# power_v1.net
KiCad netlist of a schematic drawn in EAGLE
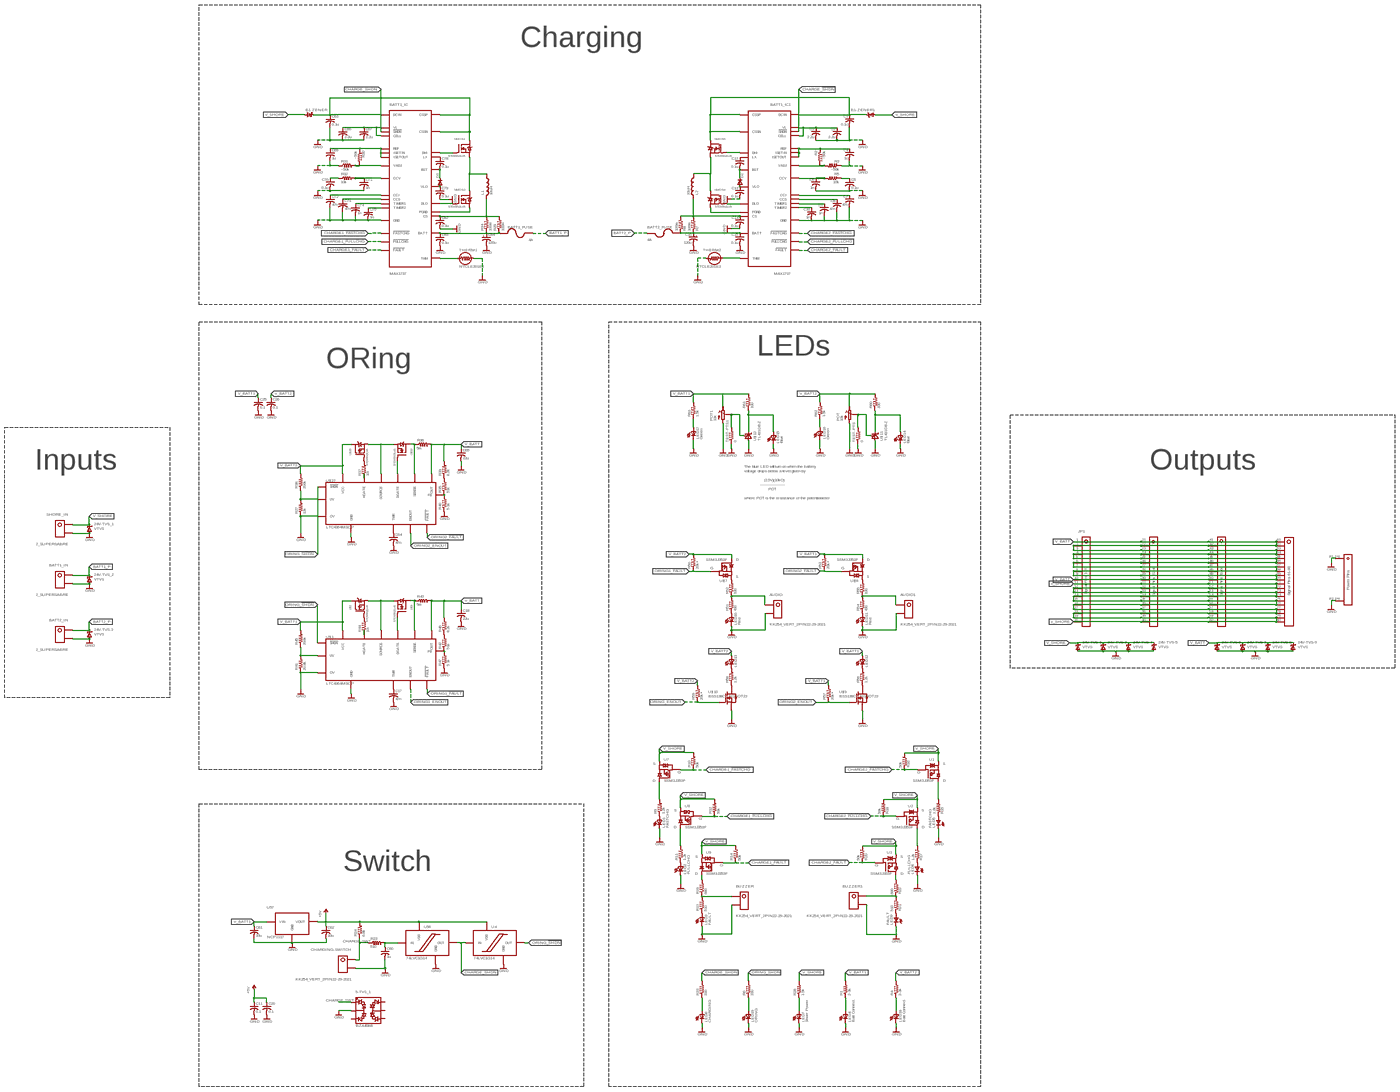
[diagram p0: schematic, sheet 1, overview]
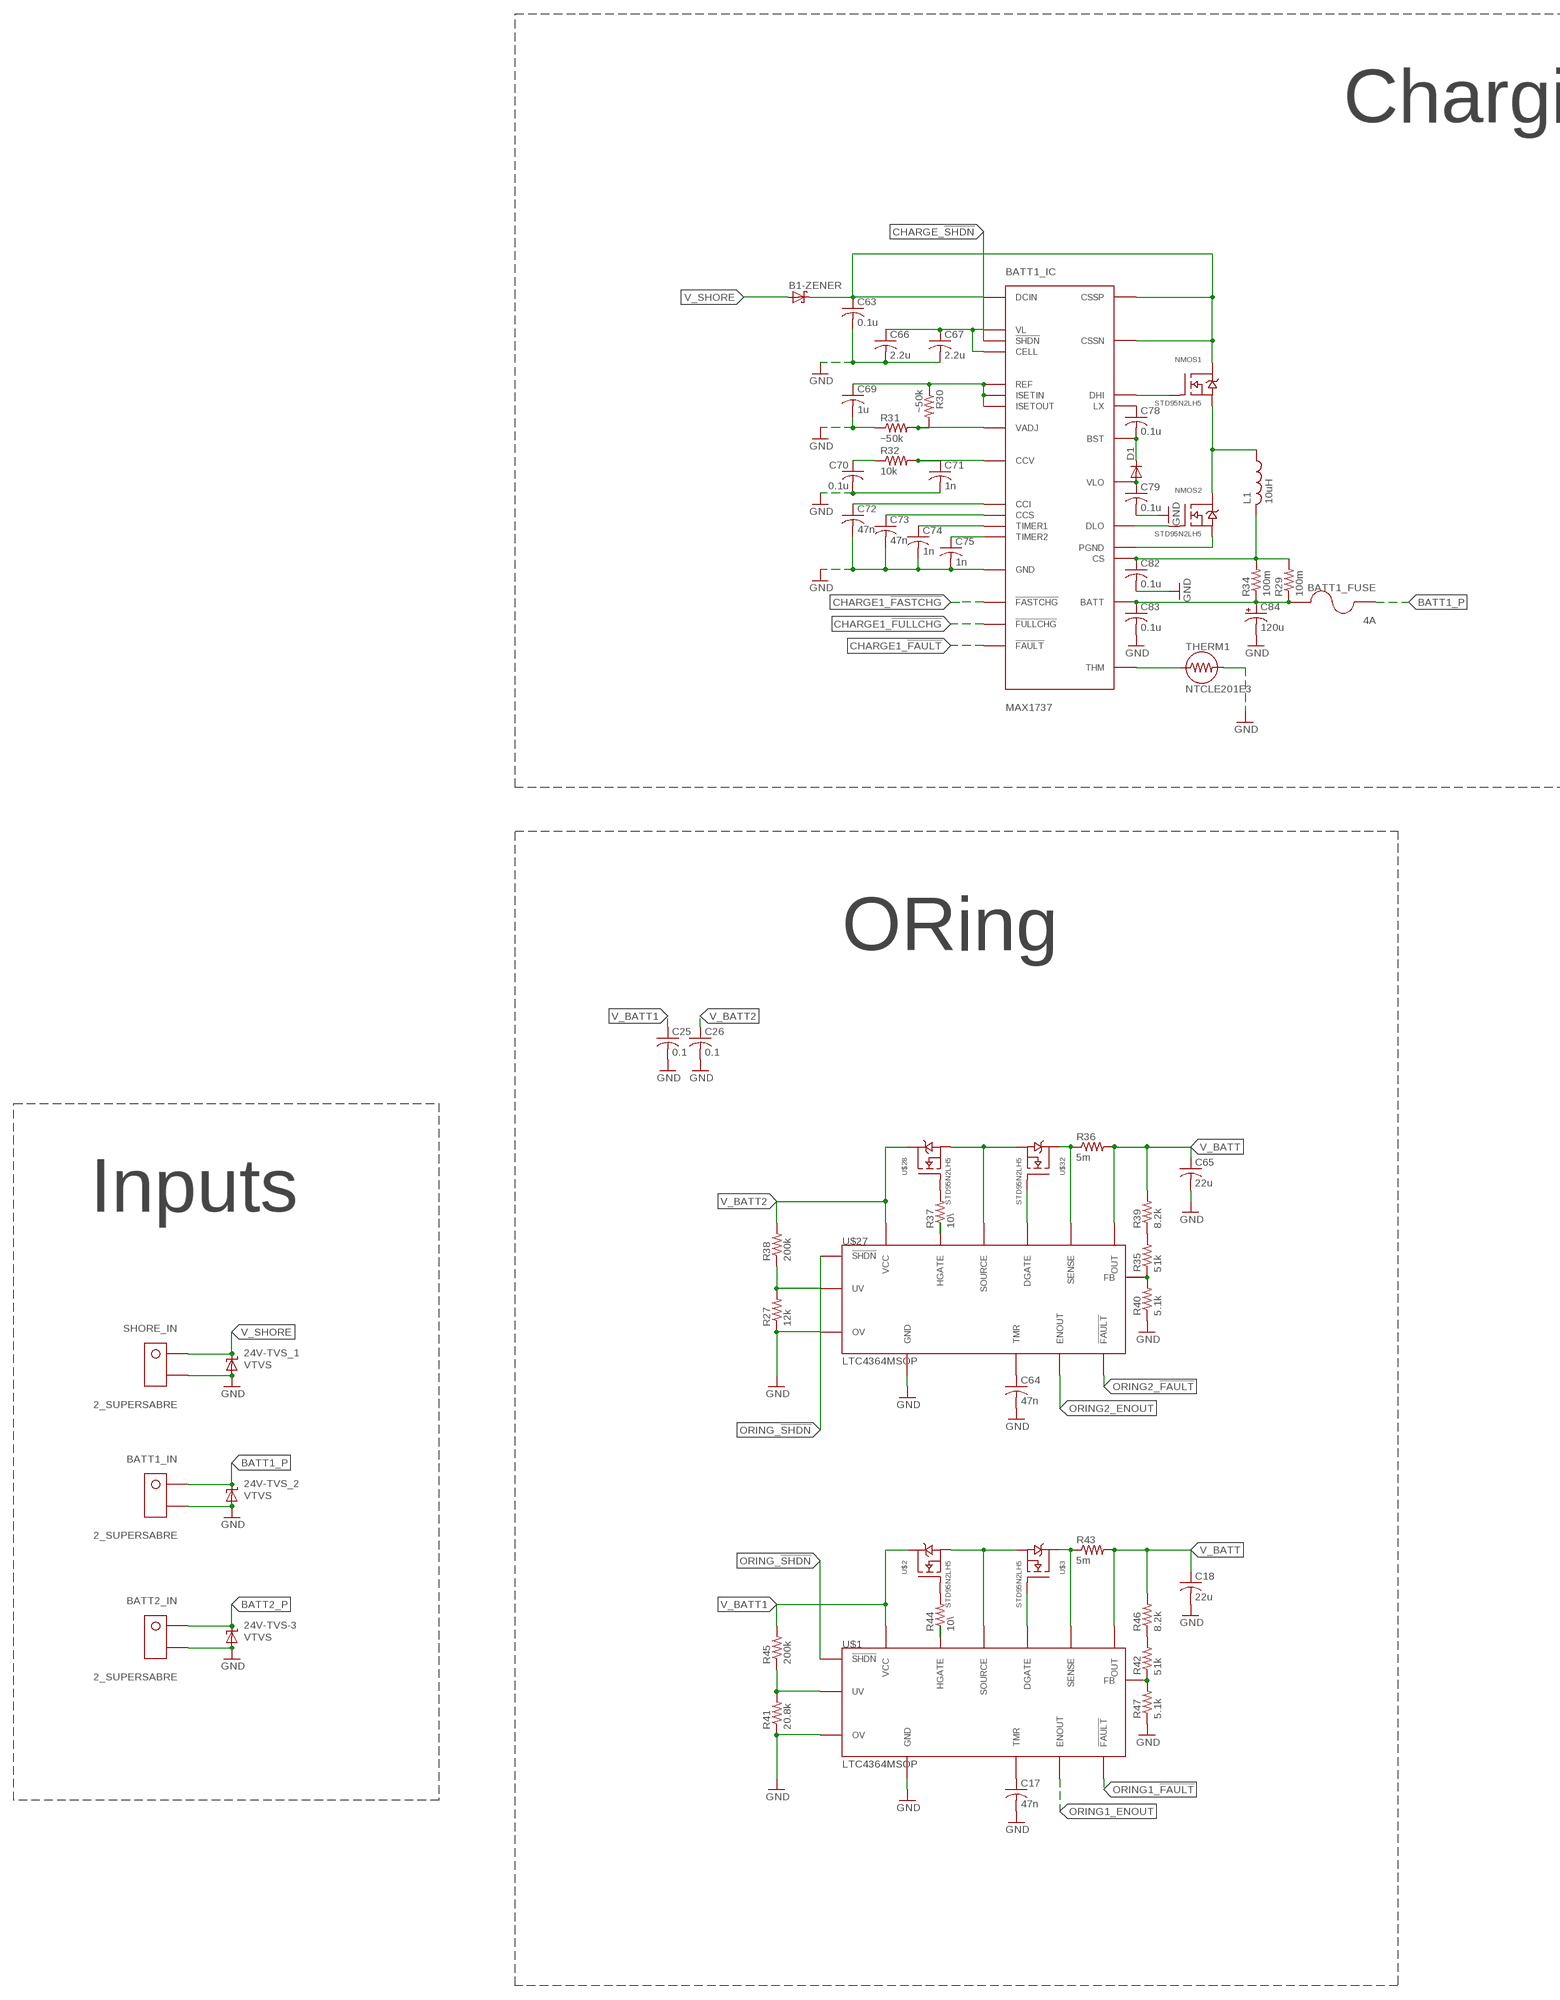
[diagram p1: schematic, sheet 1, part 1 of 4]
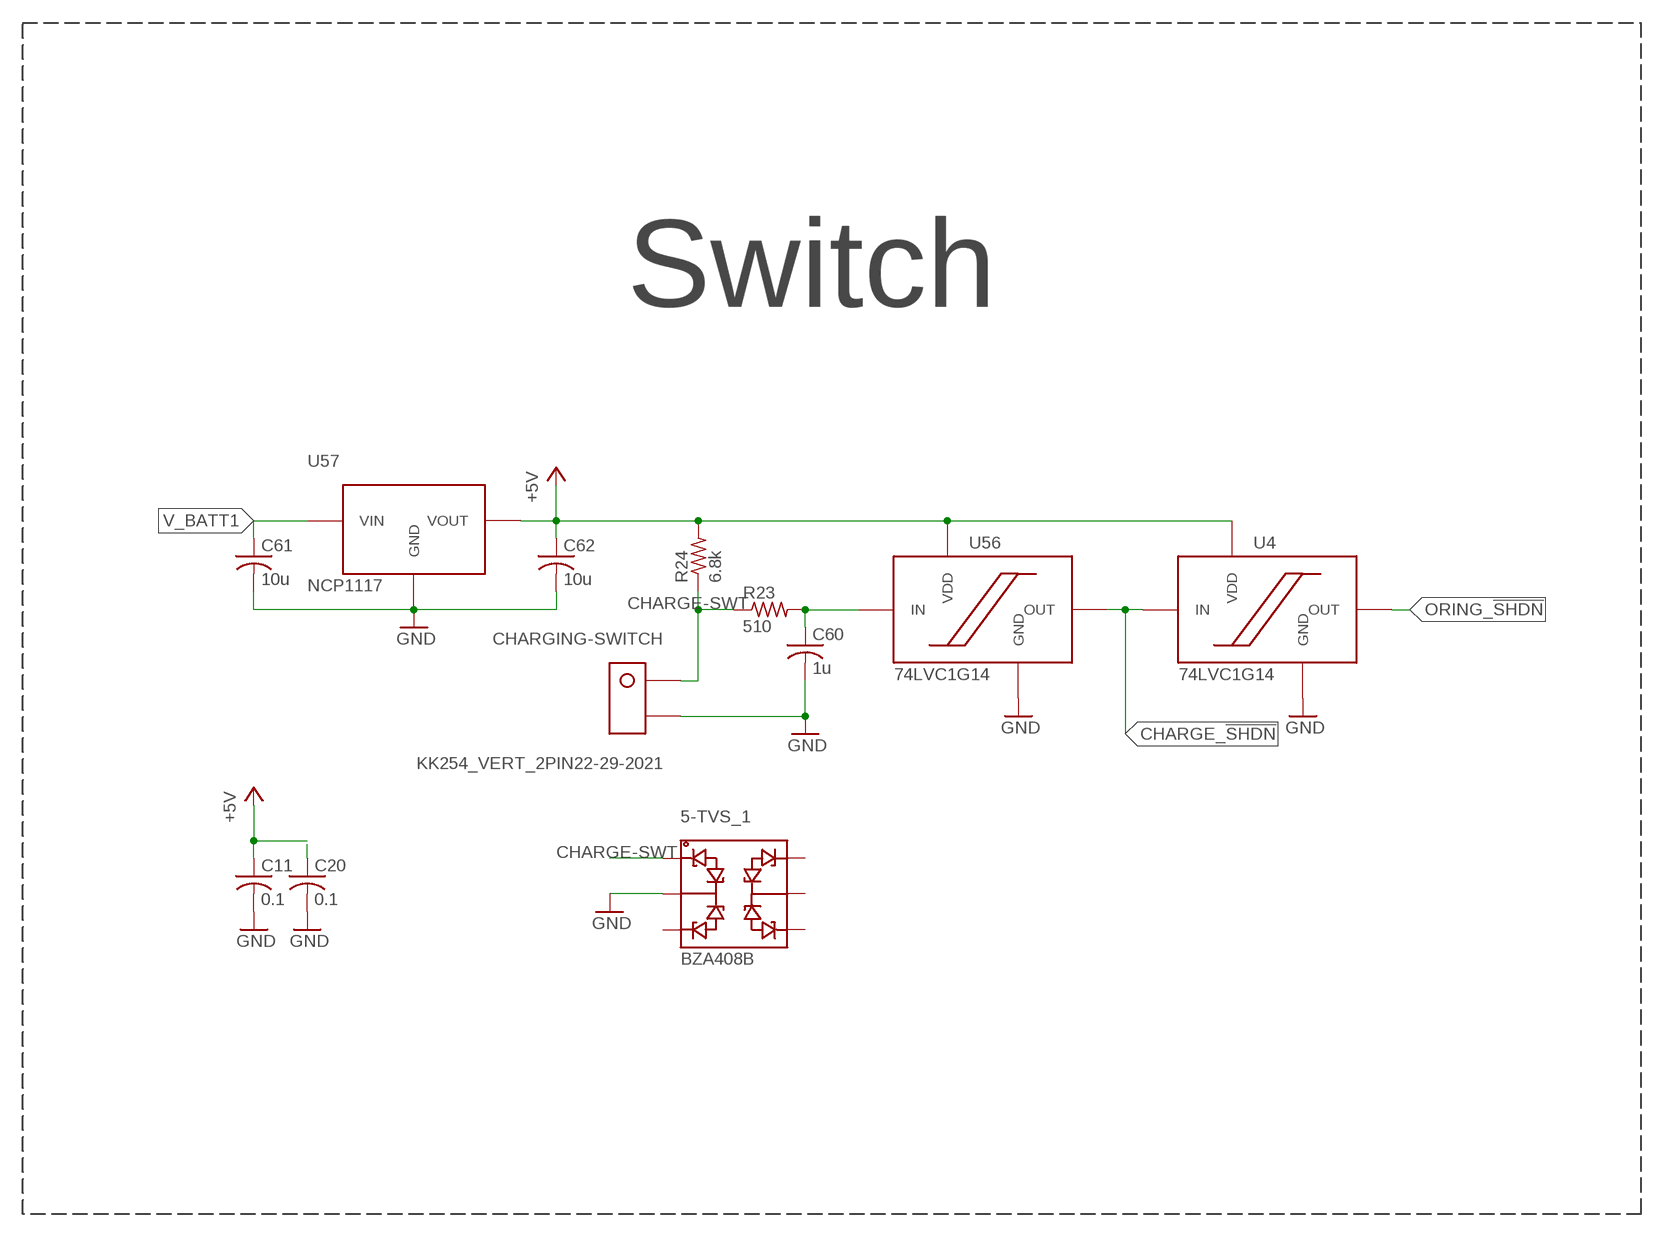
[diagram p2: schematic, sheet 1, part 2 of 4]
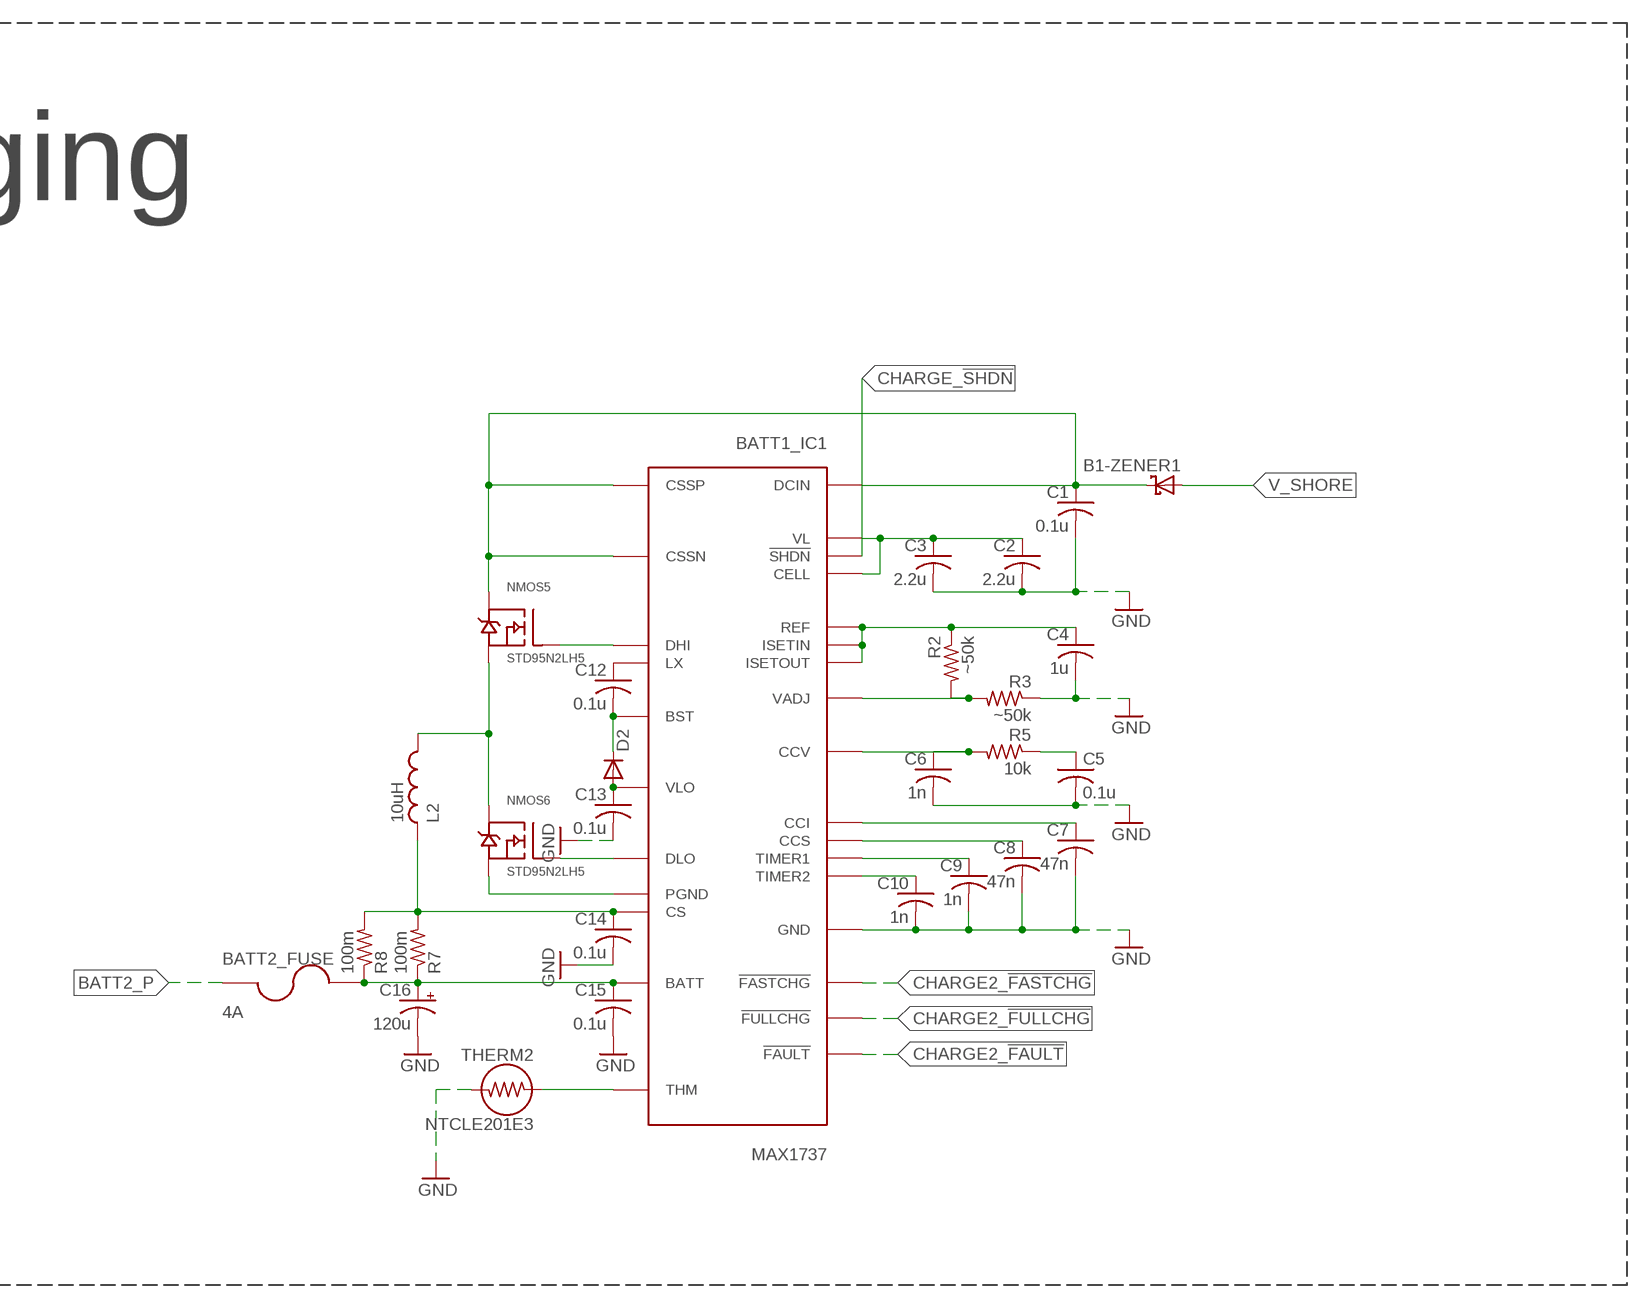
[diagram p3: schematic, sheet 1, part 3 of 4]
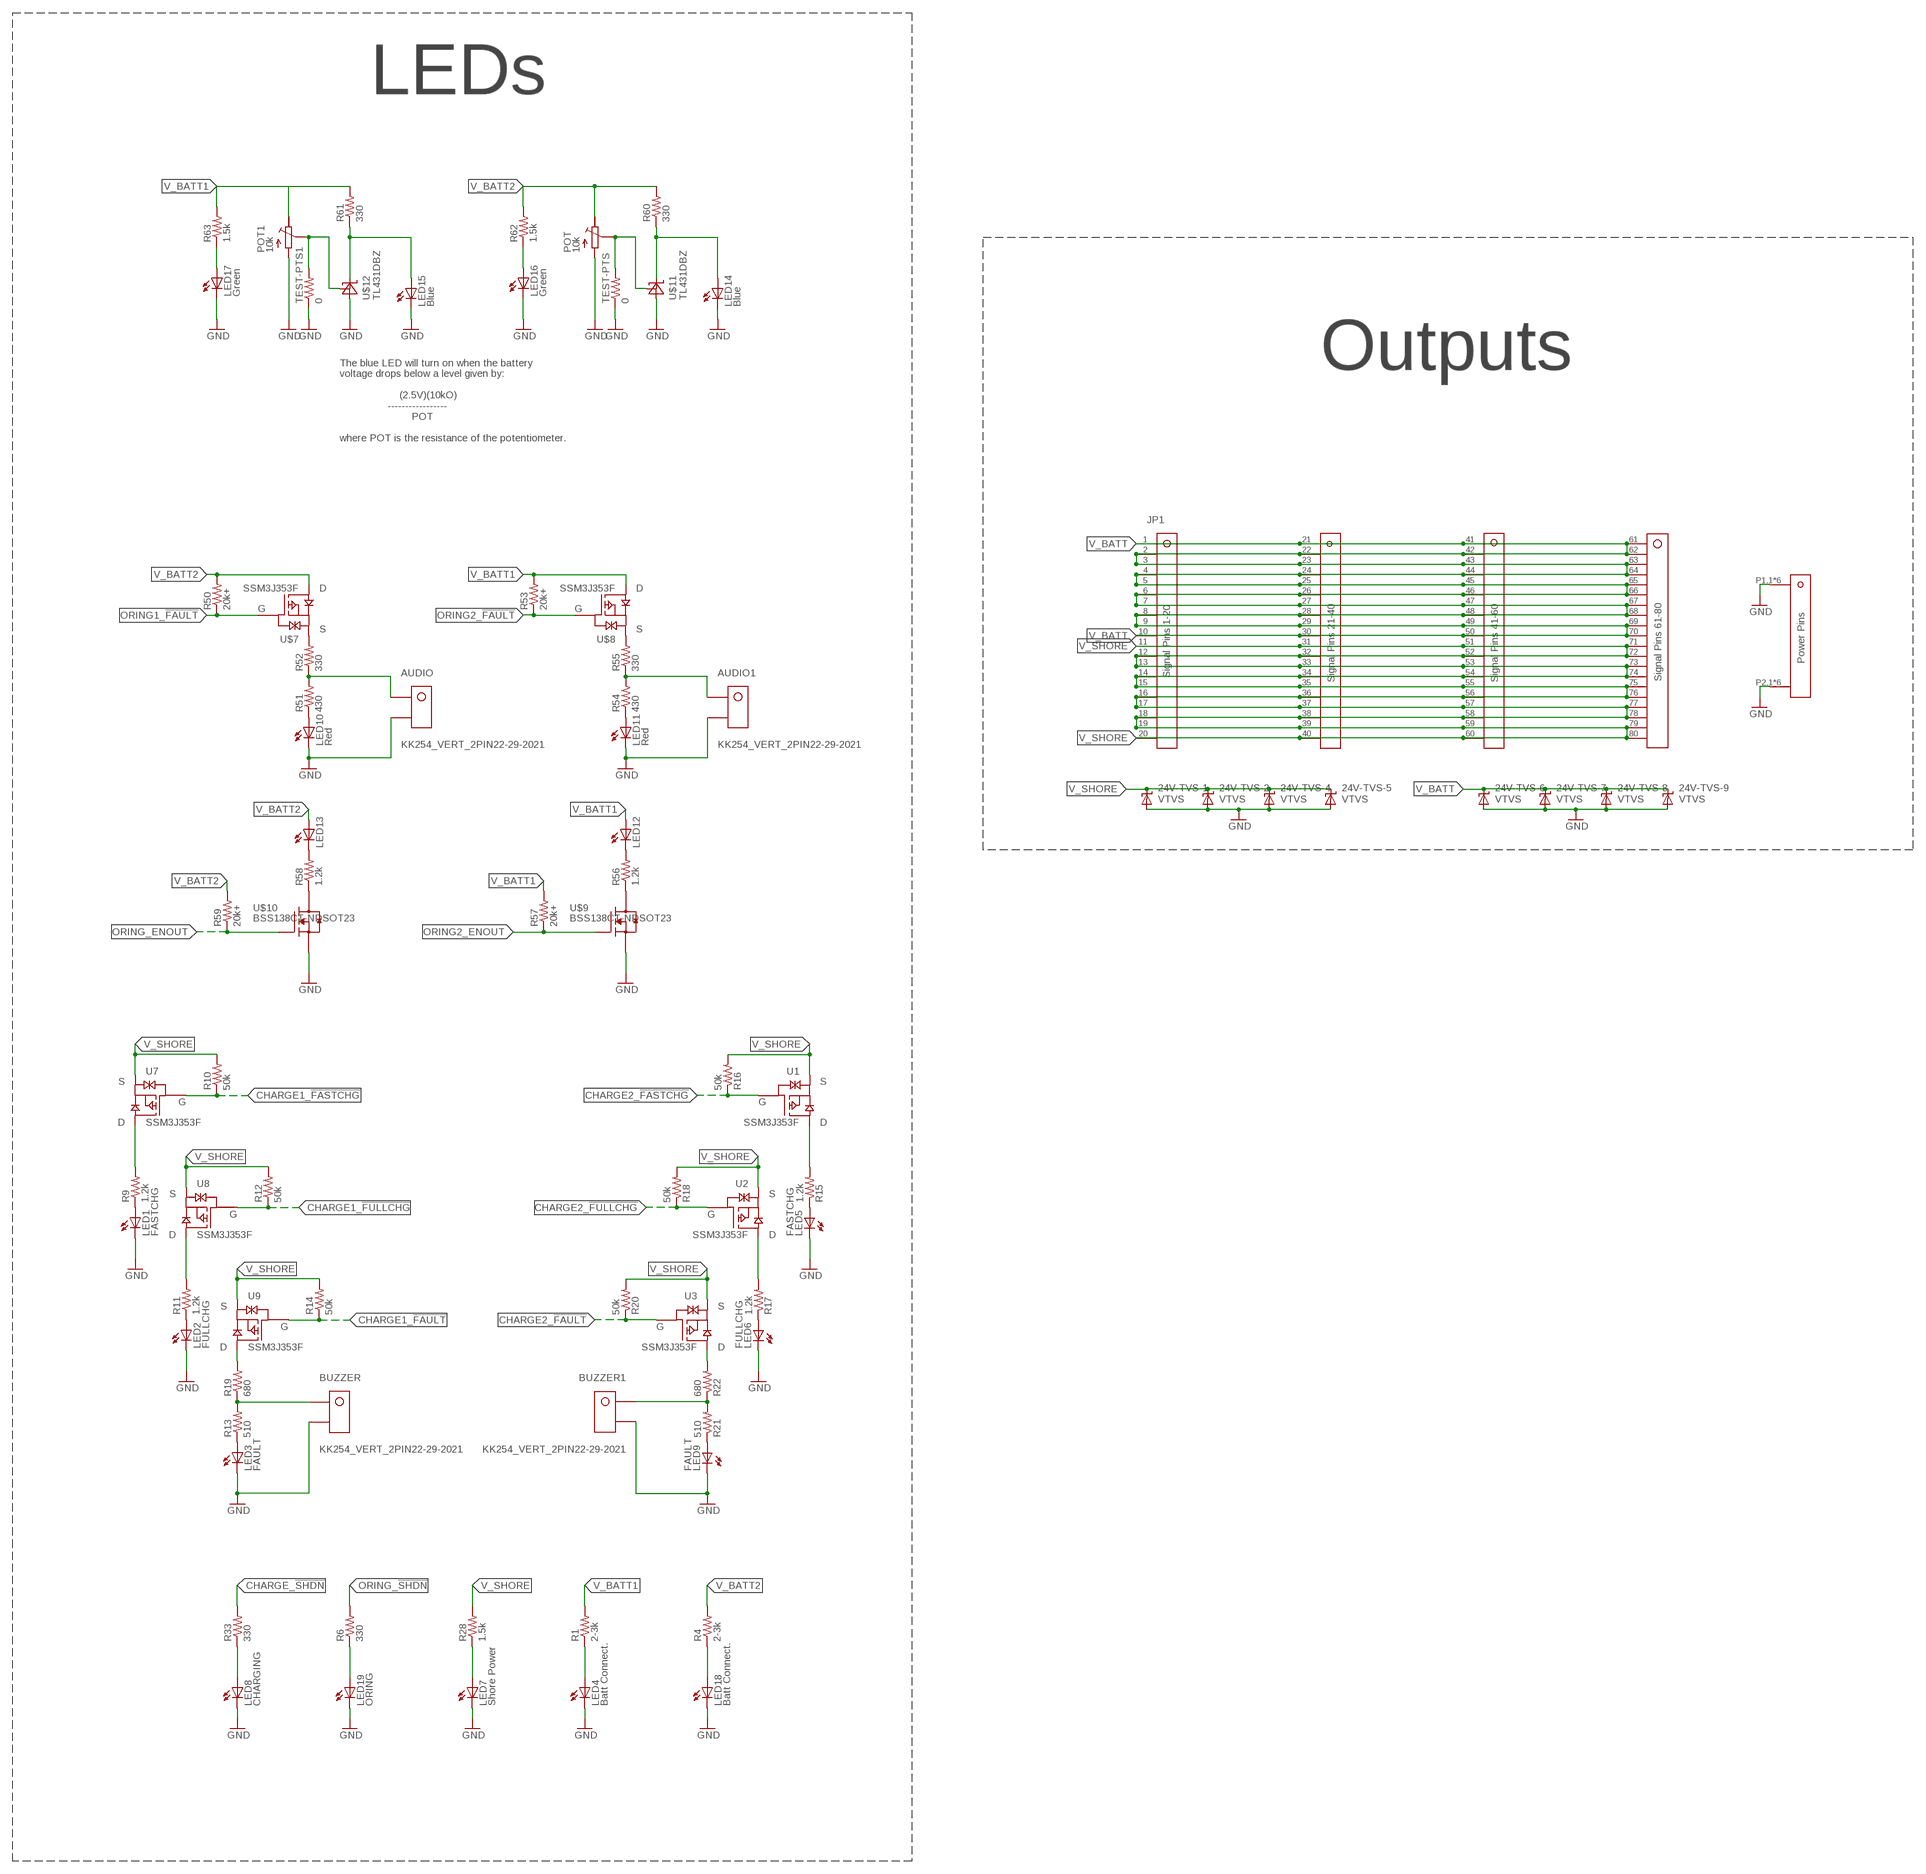
[diagram p4: schematic, sheet 1, part 4 of 4]

(export (version "E")
  (design (tool "Eeschema 10.0.6"))
  (components
    (comp (ref "5-TVS_1")
      (value "BZA408B")
      (footprint "eagle-import:SOT457")
      (libsource (lib "eagle-import") (part "BZA408B"))
    )
    (comp (ref "24V-TVS-1")
      (value "VTVS")
      (footprint "eagle-import:DO-219AB")
      (libsource (lib "eagle-import") (part "VTVS"))
    )
    (comp (ref "24V-TVS-2")
      (value "VTVS")
      (footprint "eagle-import:DO-219AB")
      (libsource (lib "eagle-import") (part "VTVS"))
    )
    (comp (ref "24V-TVS-3")
      (value "VTVS")
      (footprint "eagle-import:DO-219AB")
      (libsource (lib "eagle-import") (part "VTVS"))
    )
    (comp (ref "24V-TVS-4")
      (value "VTVS")
      (footprint "eagle-import:DO-219AB")
      (libsource (lib "eagle-import") (part "VTVS"))
    )
    (comp (ref "24V-TVS-5")
      (value "VTVS")
      (footprint "eagle-import:DO-219AB")
      (libsource (lib "eagle-import") (part "VTVS"))
    )
    (comp (ref "24V-TVS-6")
      (value "VTVS")
      (footprint "eagle-import:DO-219AB")
      (libsource (lib "eagle-import") (part "VTVS"))
    )
    (comp (ref "24V-TVS-7")
      (value "VTVS")
      (footprint "eagle-import:DO-219AB")
      (libsource (lib "eagle-import") (part "VTVS"))
    )
    (comp (ref "24V-TVS-8")
      (value "VTVS")
      (footprint "eagle-import:DO-219AB")
      (libsource (lib "eagle-import") (part "VTVS"))
    )
    (comp (ref "24V-TVS-9")
      (value "VTVS")
      (footprint "eagle-import:DO-219AB")
      (libsource (lib "eagle-import") (part "VTVS"))
    )
    (comp (ref "24V-TVS_1")
      (value "VTVS")
      (footprint "eagle-import:DO-219AB")
      (libsource (lib "eagle-import") (part "VTVS"))
    )
    (comp (ref "24V-TVS_2")
      (value "VTVS")
      (footprint "eagle-import:DO-219AB")
      (libsource (lib "eagle-import") (part "VTVS"))
    )
    (comp (ref "AUDIO")
      (value "KK254_VERT_2PIN22-29-2021")
      (footprint "eagle-import:KK254_VERT_2PIN")
      (libsource (lib "eagle-import") (part "KK254_VERT_2PIN22-29-2021"))
    )
    (comp (ref "AUDIO1")
      (value "KK254_VERT_2PIN22-29-2021")
      (footprint "eagle-import:KK254_VERT_2PIN")
      (libsource (lib "eagle-import") (part "KK254_VERT_2PIN22-29-2021"))
    )
    (comp (ref "B1-ZENER")
      (value "SCHOTTKY-DIODESOD-106")
      (footprint "eagle-import:SOD106-R")
      (libsource (lib "eagle-import") (part "SCHOTTKY-DIODESOD-106"))
    )
    (comp (ref "B1-ZENER1")
      (value "SCHOTTKY-DIODESOD-106")
      (footprint "eagle-import:SOD106-R")
      (libsource (lib "eagle-import") (part "SCHOTTKY-DIODESOD-106"))
    )
    (comp (ref "BATT1_FUSE")
      (value "4A")
      (footprint "eagle-import:154-OMNI-BLOK")
      (libsource (lib "eagle-import") (part "154-OMNI_BLOK"))
    )
    (comp (ref "BATT1_IC")
      (value "MAX1737")
      (footprint "eagle-import:QSOP28")
      (libsource (lib "eagle-import") (part "MAX1737"))
    )
    (comp (ref "BATT1_IC1")
      (value "MAX1737")
      (footprint "eagle-import:QSOP28")
      (libsource (lib "eagle-import") (part "MAX1737"))
    )
    (comp (ref "BATT1_IN")
      (value "2_SUPERSABRE")
      (footprint "eagle-import:SUPERSABRE_2CIRCUIT")
      (libsource (lib "eagle-import") (part "2_SUPERSABRE"))
    )
    (comp (ref "BATT2_FUSE")
      (value "4A")
      (footprint "eagle-import:154-OMNI-BLOK")
      (libsource (lib "eagle-import") (part "154-OMNI_BLOK"))
    )
    (comp (ref "BATT2_IN")
      (value "2_SUPERSABRE")
      (footprint "eagle-import:SUPERSABRE_2CIRCUIT")
      (libsource (lib "eagle-import") (part "2_SUPERSABRE"))
    )
    (comp (ref "BUZZER")
      (value "KK254_VERT_2PIN22-29-2021")
      (footprint "eagle-import:KK254_VERT_2PIN")
      (libsource (lib "eagle-import") (part "KK254_VERT_2PIN22-29-2021"))
    )
    (comp (ref "BUZZER1")
      (value "KK254_VERT_2PIN22-29-2021")
      (footprint "eagle-import:KK254_VERT_2PIN")
      (libsource (lib "eagle-import") (part "KK254_VERT_2PIN22-29-2021"))
    )
    (comp (ref "C1")
      (value "0.1u")
      (footprint "eagle-import:C0805")
      (libsource (lib "eagle-import") (part "C-USC0805"))
    )
    (comp (ref "C2")
      (value "2.2u")
      (footprint "eagle-import:C0805")
      (libsource (lib "eagle-import") (part "C-USC0805"))
    )
    (comp (ref "C3")
      (value "2.2u")
      (footprint "eagle-import:C0805")
      (libsource (lib "eagle-import") (part "C-USC0805"))
    )
    (comp (ref "C4")
      (value "1u")
      (footprint "eagle-import:C0805")
      (libsource (lib "eagle-import") (part "C-USC0805"))
    )
    (comp (ref "C5")
      (value "0.1u")
      (footprint "eagle-import:C0805")
      (libsource (lib "eagle-import") (part "C-USC0805"))
    )
    (comp (ref "C6")
      (value "1n")
      (footprint "eagle-import:C0805")
      (libsource (lib "eagle-import") (part "C-USC0805"))
    )
    (comp (ref "C7")
      (value "47n")
      (footprint "eagle-import:C0805")
      (libsource (lib "eagle-import") (part "C-USC0805"))
    )
    (comp (ref "C8")
      (value "47n")
      (footprint "eagle-import:C0805")
      (libsource (lib "eagle-import") (part "C-USC0805"))
    )
    (comp (ref "C9")
      (value "1n")
      (footprint "eagle-import:C0805")
      (libsource (lib "eagle-import") (part "C-USC0805"))
    )
    (comp (ref "C10")
      (value "1n")
      (footprint "eagle-import:C0805")
      (libsource (lib "eagle-import") (part "C-USC0805"))
    )
    (comp (ref "C11")
      (value "0.1")
      (footprint "eagle-import:C0805")
      (libsource (lib "eagle-import") (part "C-USC0805"))
    )
    (comp (ref "C12")
      (value "0.1u")
      (footprint "eagle-import:C0805")
      (libsource (lib "eagle-import") (part "C-USC0805"))
    )
    (comp (ref "C13")
      (value "0.1u")
      (footprint "eagle-import:C0805")
      (libsource (lib "eagle-import") (part "C-USC0805"))
    )
    (comp (ref "C14")
      (value "0.1u")
      (footprint "eagle-import:C0805")
      (libsource (lib "eagle-import") (part "C-USC0805"))
    )
    (comp (ref "C15")
      (value "0.1u")
      (footprint "eagle-import:C0805")
      (libsource (lib "eagle-import") (part "C-USC0805"))
    )
    (comp (ref "C16")
      (value "120u")
      (footprint "eagle-import:E3,5-8")
      (libsource (lib "eagle-import") (part "CPOL-USE3.5-8"))
    )
    (comp (ref "C17")
      (value "47n")
      (footprint "eagle-import:C0805")
      (libsource (lib "eagle-import") (part "C-USC0805"))
    )
    (comp (ref "C18")
      (value "22u")
      (footprint "eagle-import:C0805")
      (libsource (lib "eagle-import") (part "C-USC0805"))
    )
    (comp (ref "C20")
      (value "0.1")
      (footprint "eagle-import:C0805")
      (libsource (lib "eagle-import") (part "C-USC0805"))
    )
    (comp (ref "C25")
      (value "0.1")
      (footprint "eagle-import:C0805")
      (libsource (lib "eagle-import") (part "C-USC0805"))
    )
    (comp (ref "C26")
      (value "0.1")
      (footprint "eagle-import:C0805")
      (libsource (lib "eagle-import") (part "C-USC0805"))
    )
    (comp (ref "C60")
      (value "1u")
      (footprint "eagle-import:C0805")
      (libsource (lib "eagle-import") (part "C-USC0805"))
    )
    (comp (ref "C61")
      (value "10u")
      (footprint "eagle-import:C0805")
      (libsource (lib "eagle-import") (part "C-USC0805"))
    )
    (comp (ref "C62")
      (value "10u")
      (footprint "eagle-import:C0805")
      (libsource (lib "eagle-import") (part "C-USC0805"))
    )
    (comp (ref "C63")
      (value "0.1u")
      (footprint "eagle-import:C0805")
      (libsource (lib "eagle-import") (part "C-USC0805"))
    )
    (comp (ref "C64")
      (value "47n")
      (footprint "eagle-import:C0805")
      (libsource (lib "eagle-import") (part "C-USC0805"))
    )
    (comp (ref "C65")
      (value "22u")
      (footprint "eagle-import:C0805")
      (libsource (lib "eagle-import") (part "C-USC0805"))
    )
    (comp (ref "C66")
      (value "2.2u")
      (footprint "eagle-import:C0805")
      (libsource (lib "eagle-import") (part "C-USC0805"))
    )
    (comp (ref "C67")
      (value "2.2u")
      (footprint "eagle-import:C0805")
      (libsource (lib "eagle-import") (part "C-USC0805"))
    )
    (comp (ref "C69")
      (value "1u")
      (footprint "eagle-import:C0805")
      (libsource (lib "eagle-import") (part "C-USC0805"))
    )
    (comp (ref "C70")
      (value "0.1u")
      (footprint "eagle-import:C0805")
      (libsource (lib "eagle-import") (part "C-USC0805"))
    )
    (comp (ref "C71")
      (value "1n")
      (footprint "eagle-import:C0805")
      (libsource (lib "eagle-import") (part "C-USC0805"))
    )
    (comp (ref "C72")
      (value "47n")
      (footprint "eagle-import:C0805")
      (libsource (lib "eagle-import") (part "C-USC0805"))
    )
    (comp (ref "C73")
      (value "47n")
      (footprint "eagle-import:C0805")
      (libsource (lib "eagle-import") (part "C-USC0805"))
    )
    (comp (ref "C74")
      (value "1n")
      (footprint "eagle-import:C0805")
      (libsource (lib "eagle-import") (part "C-USC0805"))
    )
    (comp (ref "C75")
      (value "1n")
      (footprint "eagle-import:C0805")
      (libsource (lib "eagle-import") (part "C-USC0805"))
    )
    (comp (ref "C78")
      (value "0.1u")
      (footprint "eagle-import:C0805")
      (libsource (lib "eagle-import") (part "C-USC0805"))
    )
    (comp (ref "C79")
      (value "0.1u")
      (footprint "eagle-import:C0805")
      (libsource (lib "eagle-import") (part "C-USC0805"))
    )
    (comp (ref "C82")
      (value "0.1u")
      (footprint "eagle-import:C0805")
      (libsource (lib "eagle-import") (part "C-USC0805"))
    )
    (comp (ref "C83")
      (value "0.1u")
      (footprint "eagle-import:C0805")
      (libsource (lib "eagle-import") (part "C-USC0805"))
    )
    (comp (ref "C84")
      (value "120u")
      (footprint "eagle-import:E3,5-8")
      (libsource (lib "eagle-import") (part "CPOL-USE3.5-8"))
    )
    (comp (ref "CHARGING-SWITCH")
      (value "KK254_VERT_2PIN22-29-2021")
      (footprint "eagle-import:KK254_VERT_2PIN")
      (libsource (lib "eagle-import") (part "KK254_VERT_2PIN22-29-2021"))
    )
    (comp (ref "D1")
      (value "DIODE-SOD123")
      (footprint "eagle-import:SOD123")
      (libsource (lib "eagle-import") (part "DIODE-SOD123"))
    )
    (comp (ref "D2")
      (value "DIODE-SOD123")
      (footprint "eagle-import:SOD123")
      (libsource (lib "eagle-import") (part "DIODE-SOD123"))
    )
    (comp (ref "JP1")
      (value "MPSC-01-80MPSC-RA-LC")
      (footprint "eagle-import:MPSC-01-80")
      (libsource (lib "eagle-import") (part "MPSC-01-80MPSC-RA-LC"))
    )
    (comp (ref "L1")
      (value "10uH")
      (footprint "eagle-import:L6100")
      (libsource (lib "eagle-import") (part "L-USL6100"))
    )
    (comp (ref "L2")
      (value "10uH")
      (footprint "eagle-import:L6100")
      (libsource (lib "eagle-import") (part "L-USL6100"))
    )
    (comp (ref "LED1")
      (value "FASTCHG")
      (footprint "eagle-import:CHIP-LED0805")
      (libsource (lib "eagle-import") (part "LEDCHIP-LED0805"))
    )
    (comp (ref "LED2")
      (value "FULLCHG")
      (footprint "eagle-import:CHIP-LED0805")
      (libsource (lib "eagle-import") (part "LEDCHIP-LED0805"))
    )
    (comp (ref "LED3")
      (value "FAULT")
      (footprint "eagle-import:CHIP-LED0805")
      (libsource (lib "eagle-import") (part "LEDCHIP-LED0805"))
    )
    (comp (ref "LED4")
      (value "Batt Connect.")
      (footprint "eagle-import:CHIP-LED0805")
      (libsource (lib "eagle-import") (part "LEDCHIP-LED0805"))
    )
    (comp (ref "LED5")
      (value "FASTCHG")
      (footprint "eagle-import:CHIP-LED0805")
      (libsource (lib "eagle-import") (part "LEDCHIP-LED0805"))
    )
    (comp (ref "LED6")
      (value "FULLCHG")
      (footprint "eagle-import:CHIP-LED0805")
      (libsource (lib "eagle-import") (part "LEDCHIP-LED0805"))
    )
    (comp (ref "LED7")
      (value "Shore Power")
      (footprint "eagle-import:CHIP-LED0805")
      (libsource (lib "eagle-import") (part "LEDCHIP-LED0805"))
    )
    (comp (ref "LED8")
      (value "CHARGING")
      (footprint "eagle-import:CHIP-LED0805")
      (libsource (lib "eagle-import") (part "LEDCHIP-LED0805"))
    )
    (comp (ref "LED9")
      (value "FAULT")
      (footprint "eagle-import:CHIP-LED0805")
      (libsource (lib "eagle-import") (part "LEDCHIP-LED0805"))
    )
    (comp (ref "LED10")
      (value "Red")
      (footprint "eagle-import:CHIPLED_0805")
      (libsource (lib "eagle-import") (part "LEDCHIPLED_0805"))
    )
    (comp (ref "LED11")
      (value "Red")
      (footprint "eagle-import:CHIPLED_0805")
      (libsource (lib "eagle-import") (part "LEDCHIPLED_0805"))
    )
    (comp (ref "LED12")
      (value "LEDCHIPLED_0805")
      (footprint "eagle-import:CHIPLED_0805")
      (libsource (lib "eagle-import") (part "LEDCHIPLED_0805"))
    )
    (comp (ref "LED13")
      (value "LEDCHIPLED_0805")
      (footprint "eagle-import:CHIPLED_0805")
      (libsource (lib "eagle-import") (part "LEDCHIPLED_0805"))
    )
    (comp (ref "LED14")
      (value "Blue")
      (footprint "eagle-import:0805")
      (libsource (lib "eagle-import") (part "0805_LED"))
    )
    (comp (ref "LED15")
      (value "Blue")
      (footprint "eagle-import:0805")
      (libsource (lib "eagle-import") (part "0805_LED"))
    )
    (comp (ref "LED16")
      (value "Green")
      (footprint "eagle-import:0805")
      (libsource (lib "eagle-import") (part "0805_LED"))
    )
    (comp (ref "LED17")
      (value "Green")
      (footprint "eagle-import:0805")
      (libsource (lib "eagle-import") (part "0805_LED"))
    )
    (comp (ref "LED18")
      (value "Batt Connect.")
      (footprint "eagle-import:CHIP-LED0805")
      (libsource (lib "eagle-import") (part "LEDCHIP-LED0805"))
    )
    (comp (ref "LED19")
      (value "ORING")
      (footprint "eagle-import:CHIP-LED0805")
      (libsource (lib "eagle-import") (part "LEDCHIP-LED0805"))
    )
    (comp (ref "NMOS1")
      (value "STD95N2LH5")
      (footprint "eagle-import:DPAK")
      (libsource (lib "eagle-import") (part "STD95N2LH5"))
    )
    (comp (ref "NMOS2")
      (value "STD95N2LH5")
      (footprint "eagle-import:DPAK")
      (libsource (lib "eagle-import") (part "STD95N2LH5"))
    )
    (comp (ref "NMOS5")
      (value "STD95N2LH5")
      (footprint "eagle-import:DPAK")
      (libsource (lib "eagle-import") (part "STD95N2LH5"))
    )
    (comp (ref "NMOS6")
      (value "STD95N2LH5")
      (footprint "eagle-import:DPAK")
      (libsource (lib "eagle-import") (part "STD95N2LH5"))
    )
    (comp (ref "POT")
      (value "10k")
      (footprint "eagle-import:RTRIM3314J")
      (libsource (lib "eagle-import") (part "R-TRIMM3314J"))
    )
    (comp (ref "POT1")
      (value "10k")
      (footprint "eagle-import:RTRIM3314J")
      (libsource (lib "eagle-import") (part "R-TRIMM3314J"))
    )
    (comp (ref "R1")
      (value "2-3k")
      (footprint "eagle-import:R0805")
      (libsource (lib "eagle-import") (part "R-US_R0805"))
    )
    (comp (ref "R2")
      (value "~50k")
      (footprint "eagle-import:R0805")
      (libsource (lib "eagle-import") (part "R-US_R0805"))
    )
    (comp (ref "R3")
      (value "~50k")
      (footprint "eagle-import:R0805")
      (libsource (lib "eagle-import") (part "R-US_R0805"))
    )
    (comp (ref "R4")
      (value "2-3k")
      (footprint "eagle-import:R0805")
      (libsource (lib "eagle-import") (part "R-US_R0805"))
    )
    (comp (ref "R5")
      (value "10k")
      (footprint "eagle-import:R0805")
      (libsource (lib "eagle-import") (part "R-US_R0805"))
    )
    (comp (ref "R6")
      (value "330")
      (footprint "eagle-import:R0805")
      (libsource (lib "eagle-import") (part "R-US_R0805"))
    )
    (comp (ref "R7")
      (value "100m")
      (footprint "eagle-import:R2512")
      (libsource (lib "eagle-import") (part "R-US_R2512"))
    )
    (comp (ref "R8")
      (value "100m")
      (footprint "eagle-import:R2512")
      (libsource (lib "eagle-import") (part "R-US_R2512"))
    )
    (comp (ref "R9")
      (value "1.2k")
      (footprint "eagle-import:R0805")
      (libsource (lib "eagle-import") (part "R-US_R0805"))
    )
    (comp (ref "R10")
      (value "50k")
      (footprint "eagle-import:R0805")
      (libsource (lib "eagle-import") (part "R-US_R0805"))
    )
    (comp (ref "R11")
      (value "1.2k")
      (footprint "eagle-import:R0805")
      (libsource (lib "eagle-import") (part "R-US_R0805"))
    )
    (comp (ref "R12")
      (value "50k")
      (footprint "eagle-import:R0805")
      (libsource (lib "eagle-import") (part "R-US_R0805"))
    )
    (comp (ref "R13")
      (value "510")
      (footprint "eagle-import:R0805")
      (libsource (lib "eagle-import") (part "R-US_R0805"))
    )
    (comp (ref "R14")
      (value "50k")
      (footprint "eagle-import:R0805")
      (libsource (lib "eagle-import") (part "R-US_R0805"))
    )
    (comp (ref "R15")
      (value "1.2k")
      (footprint "eagle-import:R0805")
      (libsource (lib "eagle-import") (part "R-US_R0805"))
    )
    (comp (ref "R16")
      (value "50k")
      (footprint "eagle-import:R0805")
      (libsource (lib "eagle-import") (part "R-US_R0805"))
    )
    (comp (ref "R17")
      (value "1.2k")
      (footprint "eagle-import:R0805")
      (libsource (lib "eagle-import") (part "R-US_R0805"))
    )
    (comp (ref "R18")
      (value "50k")
      (footprint "eagle-import:R0805")
      (libsource (lib "eagle-import") (part "R-US_R0805"))
    )
    (comp (ref "R19")
      (value "680")
      (footprint "eagle-import:R0805")
      (libsource (lib "eagle-import") (part "R-US_R0805"))
    )
    (comp (ref "R20")
      (value "50k")
      (footprint "eagle-import:R0805")
      (libsource (lib "eagle-import") (part "R-US_R0805"))
    )
    (comp (ref "R21")
      (value "510")
      (footprint "eagle-import:R0805")
      (libsource (lib "eagle-import") (part "R-US_R0805"))
    )
    (comp (ref "R22")
      (value "680")
      (footprint "eagle-import:R0805")
      (libsource (lib "eagle-import") (part "R-US_R0805"))
    )
    (comp (ref "R23")
      (value "510")
      (footprint "eagle-import:R0805")
      (libsource (lib "eagle-import") (part "R-US_R0805"))
    )
    (comp (ref "R24")
      (value "6.8k")
      (footprint "eagle-import:R0805")
      (libsource (lib "eagle-import") (part "R-US_R0805"))
    )
    (comp (ref "R27")
      (value "12k")
      (footprint "eagle-import:R0805")
      (libsource (lib "eagle-import") (part "R-US_R0805"))
    )
    (comp (ref "R28")
      (value "1.5k")
      (footprint "eagle-import:R0805")
      (libsource (lib "eagle-import") (part "R-US_R0805"))
    )
    (comp (ref "R29")
      (value "100m")
      (footprint "eagle-import:R2512")
      (libsource (lib "eagle-import") (part "R-US_R2512"))
    )
    (comp (ref "R30")
      (value "~50k")
      (footprint "eagle-import:R0805")
      (libsource (lib "eagle-import") (part "R-US_R0805"))
    )
    (comp (ref "R31")
      (value "~50k")
      (footprint "eagle-import:R0805")
      (libsource (lib "eagle-import") (part "R-US_R0805"))
    )
    (comp (ref "R32")
      (value "10k")
      (footprint "eagle-import:R0805")
      (libsource (lib "eagle-import") (part "R-US_R0805"))
    )
    (comp (ref "R33")
      (value "330")
      (footprint "eagle-import:R0805")
      (libsource (lib "eagle-import") (part "R-US_R0805"))
    )
    (comp (ref "R34")
      (value "100m")
      (footprint "eagle-import:R2512")
      (libsource (lib "eagle-import") (part "R-US_R2512"))
    )
    (comp (ref "R35")
      (value "51k")
      (footprint "eagle-import:R0805")
      (libsource (lib "eagle-import") (part "R-US_R0805"))
    )
    (comp (ref "R36")
      (value "5m")
      (footprint "eagle-import:R0805")
      (libsource (lib "eagle-import") (part "R-US_R0805"))
    )
    (comp (ref "R37")
      (value "10\\")
      (footprint "eagle-import:R0805")
      (libsource (lib "eagle-import") (part "R-US_R0805"))
    )
    (comp (ref "R38")
      (value "200k")
      (footprint "eagle-import:R0805")
      (libsource (lib "eagle-import") (part "R-US_R0805"))
    )
    (comp (ref "R39")
      (value "8.2k")
      (footprint "eagle-import:R0805")
      (libsource (lib "eagle-import") (part "R-US_R0805"))
    )
    (comp (ref "R40")
      (value "5.1k")
      (footprint "eagle-import:R0805")
      (libsource (lib "eagle-import") (part "R-US_R0805"))
    )
    (comp (ref "R41")
      (value "20.8k")
      (footprint "eagle-import:R0805")
      (libsource (lib "eagle-import") (part "R-US_R0805"))
    )
    (comp (ref "R42")
      (value "51k")
      (footprint "eagle-import:R0805")
      (libsource (lib "eagle-import") (part "R-US_R0805"))
    )
    (comp (ref "R43")
      (value "5m")
      (footprint "eagle-import:R0805")
      (libsource (lib "eagle-import") (part "R-US_R0805"))
    )
    (comp (ref "R44")
      (value "10\\")
      (footprint "eagle-import:R0805")
      (libsource (lib "eagle-import") (part "R-US_R0805"))
    )
    (comp (ref "R45")
      (value "200k")
      (footprint "eagle-import:R0805")
      (libsource (lib "eagle-import") (part "R-US_R0805"))
    )
    (comp (ref "R46")
      (value "8.2k")
      (footprint "eagle-import:R0805")
      (libsource (lib "eagle-import") (part "R-US_R0805"))
    )
    (comp (ref "R47")
      (value "5.1k")
      (footprint "eagle-import:R0805")
      (libsource (lib "eagle-import") (part "R-US_R0805"))
    )
    (comp (ref "R50")
      (value "20k+")
      (footprint "eagle-import:R0805")
      (libsource (lib "eagle-import") (part "R-US_R0805"))
    )
    (comp (ref "R51")
      (value "430")
      (footprint "eagle-import:R0805")
      (libsource (lib "eagle-import") (part "R-US_R0805"))
    )
    (comp (ref "R52")
      (value "330")
      (footprint "eagle-import:R0805")
      (libsource (lib "eagle-import") (part "R-US_R0805"))
    )
    (comp (ref "R53")
      (value "20k+")
      (footprint "eagle-import:R0805")
      (libsource (lib "eagle-import") (part "R-US_R0805"))
    )
    (comp (ref "R54")
      (value "430")
      (footprint "eagle-import:R0805")
      (libsource (lib "eagle-import") (part "R-US_R0805"))
    )
    (comp (ref "R55")
      (value "330")
      (footprint "eagle-import:R0805")
      (libsource (lib "eagle-import") (part "R-US_R0805"))
    )
    (comp (ref "R56")
      (value "1.2k")
      (footprint "eagle-import:R0805")
      (libsource (lib "eagle-import") (part "R-US_R0805"))
    )
    (comp (ref "R57")
      (value "20k+")
      (footprint "eagle-import:R0805")
      (libsource (lib "eagle-import") (part "R-US_R0805"))
    )
    (comp (ref "R58")
      (value "1.2k")
      (footprint "eagle-import:R0805")
      (libsource (lib "eagle-import") (part "R-US_R0805"))
    )
    (comp (ref "R59")
      (value "20k+")
      (footprint "eagle-import:R0805")
      (libsource (lib "eagle-import") (part "R-US_R0805"))
    )
    (comp (ref "R60")
      (value "330")
      (footprint "eagle-import:R0805")
      (libsource (lib "eagle-import") (part "R-US_R0805"))
    )
    (comp (ref "R61")
      (value "330")
      (footprint "eagle-import:R0805")
      (libsource (lib "eagle-import") (part "R-US_R0805"))
    )
    (comp (ref "R62")
      (value "1.5k")
      (footprint "eagle-import:R0805")
      (libsource (lib "eagle-import") (part "R-US_R0805"))
    )
    (comp (ref "R63")
      (value "1.5k")
      (footprint "eagle-import:R0805")
      (libsource (lib "eagle-import") (part "R-US_R0805"))
    )
    (comp (ref "SHORE_IN")
      (value "2_SUPERSABRE")
      (footprint "eagle-import:SUPERSABRE_2CIRCUIT")
      (libsource (lib "eagle-import") (part "2_SUPERSABRE"))
    )
    (comp (ref "TEST-PTS")
      (value "0")
      (footprint "eagle-import:V526-0")
      (libsource (lib "eagle-import") (part "R-US_V526-0"))
    )
    (comp (ref "TEST-PTS1")
      (value "0")
      (footprint "eagle-import:V526-0")
      (libsource (lib "eagle-import") (part "R-US_V526-0"))
    )
    (comp (ref "THERM1")
      (value "NTCLE201E3")
      (footprint "eagle-import:2-0.3MM-LEADS")
      (libsource (lib "eagle-import") (part "NTCLE201E3"))
    )
    (comp (ref "THERM2")
      (value "NTCLE201E3")
      (footprint "eagle-import:2-0.3MM-LEADS")
      (libsource (lib "eagle-import") (part "NTCLE201E3"))
    )
    (comp (ref "U$1")
      (value "LTC4364MSOP")
      (footprint "eagle-import:MSOP16")
      (libsource (lib "eagle-import") (part "LTC4364MSOP"))
    )
    (comp (ref "U$2")
      (value "STD95N2LH5")
      (footprint "eagle-import:DPAK")
      (libsource (lib "eagle-import") (part "STD95N2LH5"))
    )
    (comp (ref "U$3")
      (value "STD95N2LH5")
      (footprint "eagle-import:DPAK")
      (libsource (lib "eagle-import") (part "STD95N2LH5"))
    )
    (comp (ref "U$7")
      (value "SSM3J353F")
      (footprint "eagle-import:SOT-346-3_S-MINI")
      (libsource (lib "eagle-import") (part "SSM3J353F"))
    )
    (comp (ref "U$8")
      (value "SSM3J353F")
      (footprint "eagle-import:SOT-346-3_S-MINI")
      (libsource (lib "eagle-import") (part "SSM3J353F"))
    )
    (comp (ref "U$9")
      (value "BSS138CT-NDSOT23")
      (footprint "eagle-import:SOT23")
      (libsource (lib "eagle-import") (part "BSS138CT-NDSOT23"))
    )
    (comp (ref "U$10")
      (value "BSS138CT-NDSOT23")
      (footprint "eagle-import:SOT23")
      (libsource (lib "eagle-import") (part "BSS138CT-NDSOT23"))
    )
    (comp (ref "U$11")
      (value "TL431DBZ")
      (footprint "eagle-import:SOT-23-3")
      (libsource (lib "eagle-import") (part "TL431DBZ"))
    )
    (comp (ref "U$12")
      (value "TL431DBZ")
      (footprint "eagle-import:SOT-23-3")
      (libsource (lib "eagle-import") (part "TL431DBZ"))
    )
    (comp (ref "U$27")
      (value "LTC4364MSOP")
      (footprint "eagle-import:MSOP16")
      (libsource (lib "eagle-import") (part "LTC4364MSOP"))
    )
    (comp (ref "U$28")
      (value "STD95N2LH5")
      (footprint "eagle-import:DPAK")
      (libsource (lib "eagle-import") (part "STD95N2LH5"))
    )
    (comp (ref "U$32")
      (value "STD95N2LH5")
      (footprint "eagle-import:DPAK")
      (libsource (lib "eagle-import") (part "STD95N2LH5"))
    )
    (comp (ref "U1")
      (value "SSM3J353F")
      (footprint "eagle-import:SOT-346-3_S-MINI")
      (libsource (lib "eagle-import") (part "SSM3J353F"))
    )
    (comp (ref "U2")
      (value "SSM3J353F")
      (footprint "eagle-import:SOT-346-3_S-MINI")
      (libsource (lib "eagle-import") (part "SSM3J353F"))
    )
    (comp (ref "U3")
      (value "SSM3J353F")
      (footprint "eagle-import:SOT-346-3_S-MINI")
      (libsource (lib "eagle-import") (part "SSM3J353F"))
    )
    (comp (ref "U4")
      (value "74LVC1G14")
      (footprint "eagle-import:TSSOP5")
      (libsource (lib "eagle-import") (part "74LVC1G14"))
    )
    (comp (ref "U7")
      (value "SSM3J353F")
      (footprint "eagle-import:SOT-346-3_S-MINI")
      (libsource (lib "eagle-import") (part "SSM3J353F"))
    )
    (comp (ref "U8")
      (value "SSM3J353F")
      (footprint "eagle-import:SOT-346-3_S-MINI")
      (libsource (lib "eagle-import") (part "SSM3J353F"))
    )
    (comp (ref "U9")
      (value "SSM3J353F")
      (footprint "eagle-import:SOT-346-3_S-MINI")
      (libsource (lib "eagle-import") (part "SSM3J353F"))
    )
    (comp (ref "U56")
      (value "74LVC1G14")
      (footprint "eagle-import:TSSOP5")
      (libsource (lib "eagle-import") (part "74LVC1G14"))
    )
    (comp (ref "U57")
      (value "NCP1117")
      (footprint "eagle-import:SOT-223")
      (libsource (lib "eagle-import") (part "NCP1117"))
    )
  )
  (nets
    (net (code "1") (name "+5V") (class "Default")
      (node (ref "C11") (pin "1") (pinfunction "1_1") (pintype "passive"))
      (node (ref "C20") (pin "1") (pinfunction "1_1") (pintype "passive"))
      (node (ref "C62") (pin "1") (pinfunction "1_1") (pintype "passive"))
      (node (ref "R24") (pin "2") (pinfunction "2_2") (pintype "passive"))
      (node (ref "U4") (pin "P$5") (pinfunction "VDD_P$5") (pintype "bidirectional"))
      (node (ref "U56") (pin "P$5") (pinfunction "VDD_P$5") (pintype "bidirectional"))
      (node (ref "U57") (pin "P$2") (pinfunction "VOUT_P$2") (pintype "bidirectional"))
      (node (ref "U57") (pin "P$4") (pinfunction "VOUT_P$4") (pintype "bidirectional"))
    )
    (net (code "2") (name "/CHARGE-SWT") (class "Default")
      (node (ref "5-TVS_1") (pin "P$1") (pinfunction "P$1_P$1") (pintype "bidirectional"))
      (node (ref "CHARGING-SWITCH") (pin "P$1") (pinfunction "P$1_P$1") (pintype "bidirectional"))
      (node (ref "R23") (pin "1") (pinfunction "1_1") (pintype "passive"))
      (node (ref "R24") (pin "1") (pinfunction "1_1") (pintype "passive"))
    )
    (net (code "3") (name "/CHARGE1_~{FASTCHG}") (class "Default")
      (node (ref "BATT1_IC") (pin "16") (pinfunction "~{FASTCHG}_16") (pintype "bidirectional"))
      (node (ref "R10") (pin "1") (pinfunction "1_1") (pintype "passive"))
      (node (ref "U7") (pin "P$1") (pinfunction "G_P$1") (pintype "bidirectional"))
    )
    (net (code "4") (name "/CHARGE1_~{FAULT}") (class "Default")
      (node (ref "BATT1_IC") (pin "15") (pinfunction "~{FAULT}_15") (pintype "bidirectional"))
      (node (ref "R14") (pin "1") (pinfunction "1_1") (pintype "passive"))
      (node (ref "U9") (pin "P$1") (pinfunction "G_P$1") (pintype "bidirectional"))
    )
    (net (code "5") (name "/CHARGE1_~{FULLCHG}") (class "Default")
      (node (ref "BATT1_IC") (pin "17") (pinfunction "~{FULLCHG}_17") (pintype "bidirectional"))
      (node (ref "R12") (pin "1") (pinfunction "1_1") (pintype "passive"))
      (node (ref "U8") (pin "P$1") (pinfunction "G_P$1") (pintype "bidirectional"))
    )
    (net (code "6") (name "/CHARGE2_~{FASTCHG}") (class "Default")
      (node (ref "BATT1_IC1") (pin "16") (pinfunction "~{FASTCHG}_16") (pintype "bidirectional"))
      (node (ref "R16") (pin "1") (pinfunction "1_1") (pintype "passive"))
      (node (ref "U1") (pin "P$1") (pinfunction "G_P$1") (pintype "bidirectional"))
    )
    (net (code "7") (name "/CHARGE2_~{FAULT}") (class "Default")
      (node (ref "BATT1_IC1") (pin "15") (pinfunction "~{FAULT}_15") (pintype "bidirectional"))
      (node (ref "R20") (pin "1") (pinfunction "1_1") (pintype "passive"))
      (node (ref "U3") (pin "P$1") (pinfunction "G_P$1") (pintype "bidirectional"))
    )
    (net (code "8") (name "/CHARGE2_~{FULLCHG}") (class "Default")
      (node (ref "BATT1_IC1") (pin "17") (pinfunction "~{FULLCHG}_17") (pintype "bidirectional"))
      (node (ref "R18") (pin "1") (pinfunction "1_1") (pintype "passive"))
      (node (ref "U2") (pin "P$1") (pinfunction "G_P$1") (pintype "bidirectional"))
    )
    (net (code "9") (name "/CHARGE_~{SHDN}") (class "Default")
      (node (ref "BATT1_IC") (pin "18") (pinfunction "~{SHDN}_18") (pintype "bidirectional"))
      (node (ref "BATT1_IC1") (pin "18") (pinfunction "~{SHDN}_18") (pintype "bidirectional"))
      (node (ref "R33") (pin "2") (pinfunction "2_2") (pintype "passive"))
      (node (ref "U4") (pin "P$2") (pinfunction "IN_P$2") (pintype "bidirectional"))
      (node (ref "U56") (pin "P$4") (pinfunction "OUT_P$4") (pintype "bidirectional"))
    )
    (net (code "10") (name "/ORING1_~{FAULT}") (class "Default")
      (node (ref "R50") (pin "1") (pinfunction "1_1") (pintype "passive"))
      (node (ref "U$1") (pin "FLT") (pinfunction "~{FAULT}_FLT") (pintype "bidirectional"))
      (node (ref "U$7") (pin "P$1") (pinfunction "G_P$1") (pintype "bidirectional"))
    )
    (net (code "11") (name "/ORING2_~{FAULT}") (class "Default")
      (node (ref "R53") (pin "1") (pinfunction "1_1") (pintype "passive"))
      (node (ref "U$27") (pin "FLT") (pinfunction "~{FAULT}_FLT") (pintype "bidirectional"))
      (node (ref "U$8") (pin "P$1") (pinfunction "G_P$1") (pintype "bidirectional"))
    )
    (net (code "12") (name "/ORING_~{SHDN}") (class "Default")
      (node (ref "R6") (pin "2") (pinfunction "2_2") (pintype "passive"))
      (node (ref "U$1") (pin "SHDN") (pinfunction "~{SHDN}_SHDN") (pintype "bidirectional"))
      (node (ref "U$27") (pin "SHDN") (pinfunction "~{SHDN}_SHDN") (pintype "bidirectional"))
      (node (ref "U4") (pin "P$4") (pinfunction "OUT_P$4") (pintype "bidirectional"))
    )
    (net (code "13") (name "BATT1_P") (class "Default")
      (node (ref "24V-TVS_2") (pin "P$2") (pinfunction "C_P$2") (pintype "passive"))
      (node (ref "BATT1_FUSE") (pin "P$1") (pinfunction "P$1_P$1") (pintype "bidirectional"))
      (node (ref "BATT1_IN") (pin "P$1") (pinfunction "P$1_P$1") (pintype "bidirectional"))
    )
    (net (code "14") (name "BATT2_P") (class "Default")
      (node (ref "24V-TVS-3") (pin "P$2") (pinfunction "C_P$2") (pintype "passive"))
      (node (ref "BATT2_FUSE") (pin "P$1") (pinfunction "P$1_P$1") (pintype "bidirectional"))
      (node (ref "BATT2_IN") (pin "P$1") (pinfunction "P$1_P$1") (pintype "bidirectional"))
    )
    (net (code "15") (name "GND") (class "Default")
      (node (ref "24V-TVS-1") (pin "P$1") (pinfunction "A_P$1") (pintype "passive"))
      (node (ref "24V-TVS-2") (pin "P$1") (pinfunction "A_P$1") (pintype "passive"))
      (node (ref "24V-TVS-3") (pin "P$1") (pinfunction "A_P$1") (pintype "passive"))
      (node (ref "24V-TVS-4") (pin "P$1") (pinfunction "A_P$1") (pintype "passive"))
      (node (ref "24V-TVS-5") (pin "P$1") (pinfunction "A_P$1") (pintype "passive"))
      (node (ref "24V-TVS-6") (pin "P$1") (pinfunction "A_P$1") (pintype "passive"))
      (node (ref "24V-TVS-7") (pin "P$1") (pinfunction "A_P$1") (pintype "passive"))
      (node (ref "24V-TVS-8") (pin "P$1") (pinfunction "A_P$1") (pintype "passive"))
      (node (ref "24V-TVS-9") (pin "P$1") (pinfunction "A_P$1") (pintype "passive"))
      (node (ref "24V-TVS_1") (pin "P$1") (pinfunction "A_P$1") (pintype "passive"))
      (node (ref "24V-TVS_2") (pin "P$1") (pinfunction "A_P$1") (pintype "passive"))
      (node (ref "5-TVS_1") (pin "P$2") (pinfunction "P$2_P$2") (pintype "bidirectional"))
      (node (ref "AUDIO") (pin "P$2") (pinfunction "P$2_P$2") (pintype "bidirectional"))
      (node (ref "AUDIO1") (pin "P$2") (pinfunction "P$2_P$2") (pintype "bidirectional"))
      (node (ref "BATT1_IC") (pin "6") (pinfunction "GND_6") (pintype "bidirectional"))
      (node (ref "BATT1_IC1") (pin "6") (pinfunction "GND_6") (pintype "bidirectional"))
      (node (ref "BATT1_IN") (pin "P$2") (pinfunction "P$2_P$2") (pintype "bidirectional"))
      (node (ref "BATT2_IN") (pin "P$2") (pinfunction "P$2_P$2") (pintype "bidirectional"))
      (node (ref "BUZZER") (pin "P$2") (pinfunction "P$2_P$2") (pintype "bidirectional"))
      (node (ref "BUZZER1") (pin "P$2") (pinfunction "P$2_P$2") (pintype "bidirectional"))
      (node (ref "C1") (pin "2") (pinfunction "2_2") (pintype "passive"))
      (node (ref "C10") (pin "2") (pinfunction "2_2") (pintype "passive"))
      (node (ref "C11") (pin "2") (pinfunction "2_2") (pintype "passive"))
      (node (ref "C13") (pin "2") (pinfunction "2_2") (pintype "passive"))
      (node (ref "C14") (pin "2") (pinfunction "2_2") (pintype "passive"))
      (node (ref "C15") (pin "2") (pinfunction "2_2") (pintype "passive"))
      (node (ref "C16") (pin "-") (pinfunction "-_-") (pintype "passive"))
      (node (ref "C17") (pin "2") (pinfunction "2_2") (pintype "passive"))
      (node (ref "C18") (pin "2") (pinfunction "2_2") (pintype "passive"))
      (node (ref "C2") (pin "2") (pinfunction "2_2") (pintype "passive"))
      (node (ref "C20") (pin "2") (pinfunction "2_2") (pintype "passive"))
      (node (ref "C25") (pin "2") (pinfunction "2_2") (pintype "passive"))
      (node (ref "C26") (pin "2") (pinfunction "2_2") (pintype "passive"))
      (node (ref "C3") (pin "2") (pinfunction "2_2") (pintype "passive"))
      (node (ref "C4") (pin "2") (pinfunction "2_2") (pintype "passive"))
      (node (ref "C5") (pin "2") (pinfunction "2_2") (pintype "passive"))
      (node (ref "C6") (pin "2") (pinfunction "2_2") (pintype "passive"))
      (node (ref "C60") (pin "2") (pinfunction "2_2") (pintype "passive"))
      (node (ref "C61") (pin "2") (pinfunction "2_2") (pintype "passive"))
      (node (ref "C62") (pin "2") (pinfunction "2_2") (pintype "passive"))
      (node (ref "C63") (pin "2") (pinfunction "2_2") (pintype "passive"))
      (node (ref "C64") (pin "2") (pinfunction "2_2") (pintype "passive"))
      (node (ref "C65") (pin "2") (pinfunction "2_2") (pintype "passive"))
      (node (ref "C66") (pin "2") (pinfunction "2_2") (pintype "passive"))
      (node (ref "C67") (pin "2") (pinfunction "2_2") (pintype "passive"))
      (node (ref "C69") (pin "2") (pinfunction "2_2") (pintype "passive"))
      (node (ref "C7") (pin "2") (pinfunction "2_2") (pintype "passive"))
      (node (ref "C70") (pin "2") (pinfunction "2_2") (pintype "passive"))
      (node (ref "C71") (pin "2") (pinfunction "2_2") (pintype "passive"))
      (node (ref "C72") (pin "2") (pinfunction "2_2") (pintype "passive"))
      (node (ref "C73") (pin "2") (pinfunction "2_2") (pintype "passive"))
      (node (ref "C74") (pin "2") (pinfunction "2_2") (pintype "passive"))
      (node (ref "C75") (pin "2") (pinfunction "2_2") (pintype "passive"))
      (node (ref "C79") (pin "2") (pinfunction "2_2") (pintype "passive"))
      (node (ref "C8") (pin "2") (pinfunction "2_2") (pintype "passive"))
      (node (ref "C82") (pin "2") (pinfunction "2_2") (pintype "passive"))
      (node (ref "C83") (pin "2") (pinfunction "2_2") (pintype "passive"))
      (node (ref "C84") (pin "-") (pinfunction "-_-") (pintype "passive"))
      (node (ref "C9") (pin "2") (pinfunction "2_2") (pintype "passive"))
      (node (ref "CHARGING-SWITCH") (pin "P$2") (pinfunction "P$2_P$2") (pintype "bidirectional"))
      (node (ref "JP1") (pin "P1,1") (pinfunction "POWER1_P1,1") (pintype "bidirectional"))
      (node (ref "JP1") (pin "P1,2") (pinfunction "POWER1_P1,2") (pintype "bidirectional"))
      (node (ref "JP1") (pin "P1,3") (pinfunction "POWER1_P1,3") (pintype "bidirectional"))
      (node (ref "JP1") (pin "P1,4") (pinfunction "POWER1_P1,4") (pintype "bidirectional"))
      (node (ref "JP1") (pin "P1,5") (pinfunction "POWER1_P1,5") (pintype "bidirectional"))
      (node (ref "JP1") (pin "P1,6") (pinfunction "POWER1_P1,6") (pintype "bidirectional"))
      (node (ref "JP1") (pin "P2,1") (pinfunction "POWER2_P2,1") (pintype "bidirectional"))
      (node (ref "JP1") (pin "P2,2") (pinfunction "POWER2_P2,2") (pintype "bidirectional"))
      (node (ref "JP1") (pin "P2,3") (pinfunction "POWER2_P2,3") (pintype "bidirectional"))
      (node (ref "JP1") (pin "P2,4") (pinfunction "POWER2_P2,4") (pintype "bidirectional"))
      (node (ref "JP1") (pin "P2,5") (pinfunction "POWER2_P2,5") (pintype "bidirectional"))
      (node (ref "JP1") (pin "P2,6") (pinfunction "POWER2_P2,6") (pintype "bidirectional"))
      (node (ref "LED1") (pin "C") (pinfunction "C_C") (pintype "passive"))
      (node (ref "LED10") (pin "C") (pinfunction "C_C") (pintype "passive"))
      (node (ref "LED11") (pin "C") (pinfunction "C_C") (pintype "passive"))
      (node (ref "LED14") (pin "P$2") (pinfunction "C_P$2") (pintype "passive"))
      (node (ref "LED15") (pin "P$2") (pinfunction "C_P$2") (pintype "passive"))
      (node (ref "LED16") (pin "P$2") (pinfunction "C_P$2") (pintype "passive"))
      (node (ref "LED17") (pin "P$2") (pinfunction "C_P$2") (pintype "passive"))
      (node (ref "LED18") (pin "C") (pinfunction "C_C") (pintype "passive"))
      (node (ref "LED19") (pin "C") (pinfunction "C_C") (pintype "passive"))
      (node (ref "LED2") (pin "C") (pinfunction "C_C") (pintype "passive"))
      (node (ref "LED3") (pin "C") (pinfunction "C_C") (pintype "passive"))
      (node (ref "LED4") (pin "C") (pinfunction "C_C") (pintype "passive"))
      (node (ref "LED5") (pin "C") (pinfunction "C_C") (pintype "passive"))
      (node (ref "LED6") (pin "C") (pinfunction "C_C") (pintype "passive"))
      (node (ref "LED7") (pin "C") (pinfunction "C_C") (pintype "passive"))
      (node (ref "LED8") (pin "C") (pinfunction "C_C") (pintype "passive"))
      (node (ref "LED9") (pin "C") (pinfunction "C_C") (pintype "passive"))
      (node (ref "POT") (pin "1") (pinfunction "E_1") (pintype "passive"))
      (node (ref "POT1") (pin "1") (pinfunction "E_1") (pintype "passive"))
      (node (ref "R27") (pin "1") (pinfunction "1_1") (pintype "passive"))
      (node (ref "R3") (pin "1") (pinfunction "1_1") (pintype "passive"))
      (node (ref "R31") (pin "1") (pinfunction "1_1") (pintype "passive"))
      (node (ref "R40") (pin "1") (pinfunction "1_1") (pintype "passive"))
      (node (ref "R41") (pin "1") (pinfunction "1_1") (pintype "passive"))
      (node (ref "R47") (pin "1") (pinfunction "1_1") (pintype "passive"))
      (node (ref "SHORE_IN") (pin "P$2") (pinfunction "P$2_P$2") (pintype "bidirectional"))
      (node (ref "TEST-PTS") (pin "1") (pinfunction "1_1") (pintype "passive"))
      (node (ref "TEST-PTS1") (pin "1") (pinfunction "1_1") (pintype "passive"))
      (node (ref "THERM1") (pin "P$2") (pinfunction "2_P$2") (pintype "passive"))
      (node (ref "THERM2") (pin "P$2") (pinfunction "2_P$2") (pintype "passive"))
      (node (ref "U$1") (pin "GND") (pinfunction "GND_GND") (pintype "bidirectional"))
      (node (ref "U$1") (pin "OV") (pinfunction "OV_OV") (pintype "bidirectional"))
      (node (ref "U$10") (pin "2") (pinfunction "S_2") (pintype "passive"))
      (node (ref "U$11") (pin "P$3") (pinfunction "A_P$3") (pintype "passive"))
      (node (ref "U$12") (pin "P$3") (pinfunction "A_P$3") (pintype "passive"))
      (node (ref "U$27") (pin "GND") (pinfunction "GND_GND") (pintype "bidirectional"))
      (node (ref "U$27") (pin "OV") (pinfunction "OV_OV") (pintype "bidirectional"))
      (node (ref "U$9") (pin "2") (pinfunction "S_2") (pintype "passive"))
      (node (ref "U4") (pin "P$3") (pinfunction "GND_P$3") (pintype "bidirectional"))
      (node (ref "U56") (pin "P$3") (pinfunction "GND_P$3") (pintype "bidirectional"))
      (node (ref "U57") (pin "P$1") (pinfunction "GND_P$1") (pintype "bidirectional"))
    )
    (net (code "16") (name "Net-(AUDIO-PadP$1)") (class "Default")
      (node (ref "AUDIO") (pin "P$1") (pinfunction "P$1_P$1") (pintype "bidirectional"))
      (node (ref "R51") (pin "2") (pinfunction "2_2") (pintype "passive"))
      (node (ref "R52") (pin "1") (pinfunction "1_1") (pintype "passive"))
    )
    (net (code "17") (name "Net-(AUDIO1-PadP$1)") (class "Default")
      (node (ref "AUDIO1") (pin "P$1") (pinfunction "P$1_P$1") (pintype "bidirectional"))
      (node (ref "R54") (pin "2") (pinfunction "2_2") (pintype "passive"))
      (node (ref "R55") (pin "1") (pinfunction "1_1") (pintype "passive"))
    )
    (net (code "18") (name "Net-(BATT1_IC-BATT)") (class "Default")
      (node (ref "BATT1_FUSE") (pin "P$2") (pinfunction "P$2_P$2") (pintype "bidirectional"))
      (node (ref "BATT1_IC") (pin "7") (pinfunction "BATT_7") (pintype "bidirectional"))
      (node (ref "C83") (pin "1") (pinfunction "1_1") (pintype "passive"))
      (node (ref "C84") (pin "+") (pinfunction "+_+") (pintype "passive"))
      (node (ref "R29") (pin "1") (pinfunction "1_1") (pintype "passive"))
      (node (ref "R34") (pin "1") (pinfunction "1_1") (pintype "passive"))
    )
    (net (code "19") (name "Net-(BATT1_IC-BST)") (class "Default")
      (node (ref "BATT1_IC") (pin "23") (pinfunction "BST_23") (pintype "bidirectional"))
      (node (ref "C78") (pin "2") (pinfunction "2_2") (pintype "passive"))
      (node (ref "D1") (pin "C") (pinfunction "C_C") (pintype "passive"))
    )
    (net (code "20") (name "Net-(BATT1_IC-CCI)") (class "Default")
      (node (ref "BATT1_IC") (pin "11") (pinfunction "CCI_11") (pintype "bidirectional"))
      (node (ref "C72") (pin "1") (pinfunction "1_1") (pintype "passive"))
    )
    (net (code "21") (name "Net-(BATT1_IC-CCS)") (class "Default")
      (node (ref "BATT1_IC") (pin "10") (pinfunction "CCS_10") (pintype "bidirectional"))
      (node (ref "C73") (pin "1") (pinfunction "1_1") (pintype "passive"))
    )
    (net (code "22") (name "Net-(BATT1_IC-CCV)") (class "Default")
      (node (ref "BATT1_IC") (pin "9") (pinfunction "CCV_9") (pintype "bidirectional"))
      (node (ref "C71") (pin "1") (pinfunction "1_1") (pintype "passive"))
      (node (ref "R32") (pin "2") (pinfunction "2_2") (pintype "passive"))
    )
    (net (code "23") (name "Net-(BATT1_IC-CELL)") (class "Default")
      (node (ref "BATT1_IC") (pin "1") (pinfunction "VL_1") (pintype "bidirectional"))
      (node (ref "BATT1_IC") (pin "12") (pinfunction "CELL_12") (pintype "bidirectional"))
      (node (ref "C66") (pin "1") (pinfunction "1_1") (pintype "passive"))
      (node (ref "C67") (pin "1") (pinfunction "1_1") (pintype "passive"))
    )
    (net (code "24") (name "Net-(BATT1_IC-CS)") (class "Default")
      (node (ref "BATT1_IC") (pin "19") (pinfunction "CS_19") (pintype "bidirectional"))
      (node (ref "C82") (pin "1") (pinfunction "1_1") (pintype "passive"))
      (node (ref "L1") (pin "P$2") (pinfunction "2_P$2") (pintype "passive"))
      (node (ref "R29") (pin "2") (pinfunction "2_2") (pintype "passive"))
      (node (ref "R34") (pin "2") (pinfunction "2_2") (pintype "passive"))
    )
    (net (code "25") (name "Net-(BATT1_IC-CSSN)") (class "Default")
      (node (ref "B1-ZENER") (pin "C") (pinfunction "C_C") (pintype "passive"))
      (node (ref "BATT1_IC") (pin "26") (pinfunction "CSSN_26") (pintype "bidirectional"))
      (node (ref "BATT1_IC") (pin "27") (pinfunction "CSSP_27") (pintype "bidirectional"))
      (node (ref "BATT1_IC") (pin "28") (pinfunction "DCIN_28") (pintype "bidirectional"))
      (node (ref "C63") (pin "1") (pinfunction "1_1") (pintype "passive"))
      (node (ref "NMOS1") (pin "TAB") (pinfunction "D_TAB") (pintype "bidirectional"))
    )
    (net (code "26") (name "Net-(BATT1_IC-DHI)") (class "Default")
      (node (ref "BATT1_IC") (pin "25") (pinfunction "DHI_25") (pintype "bidirectional"))
      (node (ref "NMOS1") (pin "1") (pinfunction "G_1") (pintype "bidirectional"))
    )
    (net (code "27") (name "Net-(BATT1_IC-DLO)") (class "Default")
      (node (ref "BATT1_IC") (pin "21") (pinfunction "DLO_21") (pintype "bidirectional"))
      (node (ref "NMOS2") (pin "1") (pinfunction "G_1") (pintype "bidirectional"))
    )
    (net (code "28") (name "Net-(BATT1_IC-ISETIN)") (class "Default")
      (node (ref "BATT1_IC") (pin "2") (pinfunction "ISETIN_2") (pintype "bidirectional"))
      (node (ref "BATT1_IC") (pin "3") (pinfunction "ISETOUT_3") (pintype "bidirectional"))
      (node (ref "BATT1_IC") (pin "5") (pinfunction "REF_5") (pintype "bidirectional"))
      (node (ref "C69") (pin "1") (pinfunction "1_1") (pintype "passive"))
      (node (ref "R30") (pin "1") (pinfunction "1_1") (pintype "passive"))
    )
    (net (code "29") (name "Net-(BATT1_IC-LX)") (class "Default")
      (node (ref "BATT1_IC") (pin "24") (pinfunction "LX_24") (pintype "bidirectional"))
      (node (ref "C78") (pin "1") (pinfunction "1_1") (pintype "passive"))
    )
    (net (code "30") (name "Net-(BATT1_IC-PGND)") (class "Default")
      (node (ref "BATT1_IC") (pin "20") (pinfunction "PGND_20") (pintype "bidirectional"))
      (node (ref "NMOS2") (pin "3") (pinfunction "S_3") (pintype "bidirectional"))
    )
    (net (code "31") (name "Net-(BATT1_IC-THM)") (class "Default")
      (node (ref "BATT1_IC") (pin "4") (pinfunction "THM_4") (pintype "bidirectional"))
      (node (ref "THERM1") (pin "P$1") (pinfunction "1_P$1") (pintype "passive"))
    )
    (net (code "32") (name "Net-(BATT1_IC-TIMER1)") (class "Default")
      (node (ref "BATT1_IC") (pin "13") (pinfunction "TIMER1_13") (pintype "bidirectional"))
      (node (ref "C74") (pin "1") (pinfunction "1_1") (pintype "passive"))
    )
    (net (code "33") (name "Net-(BATT1_IC-TIMER2)") (class "Default")
      (node (ref "BATT1_IC") (pin "14") (pinfunction "TIMER2_14") (pintype "bidirectional"))
      (node (ref "C75") (pin "1") (pinfunction "1_1") (pintype "passive"))
    )
    (net (code "34") (name "Net-(BATT1_IC-VADJ)") (class "Default")
      (node (ref "BATT1_IC") (pin "8") (pinfunction "VADJ_8") (pintype "bidirectional"))
      (node (ref "R30") (pin "2") (pinfunction "2_2") (pintype "passive"))
      (node (ref "R31") (pin "2") (pinfunction "2_2") (pintype "passive"))
    )
    (net (code "35") (name "Net-(BATT1_IC-VLO)") (class "Default")
      (node (ref "BATT1_IC") (pin "22") (pinfunction "VLO_22") (pintype "bidirectional"))
      (node (ref "C79") (pin "1") (pinfunction "1_1") (pintype "passive"))
      (node (ref "D1") (pin "A") (pinfunction "A_A") (pintype "passive"))
    )
    (net (code "36") (name "Net-(BATT1_IC1-BATT)") (class "Default")
      (node (ref "BATT1_IC1") (pin "7") (pinfunction "BATT_7") (pintype "bidirectional"))
      (node (ref "BATT2_FUSE") (pin "P$2") (pinfunction "P$2_P$2") (pintype "bidirectional"))
      (node (ref "C15") (pin "1") (pinfunction "1_1") (pintype "passive"))
      (node (ref "C16") (pin "+") (pinfunction "+_+") (pintype "passive"))
      (node (ref "R7") (pin "1") (pinfunction "1_1") (pintype "passive"))
      (node (ref "R8") (pin "1") (pinfunction "1_1") (pintype "passive"))
    )
    (net (code "37") (name "Net-(BATT1_IC1-BST)") (class "Default")
      (node (ref "BATT1_IC1") (pin "23") (pinfunction "BST_23") (pintype "bidirectional"))
      (node (ref "C12") (pin "2") (pinfunction "2_2") (pintype "passive"))
      (node (ref "D2") (pin "C") (pinfunction "C_C") (pintype "passive"))
    )
    (net (code "38") (name "Net-(BATT1_IC1-CCI)") (class "Default")
      (node (ref "BATT1_IC1") (pin "11") (pinfunction "CCI_11") (pintype "bidirectional"))
      (node (ref "C7") (pin "1") (pinfunction "1_1") (pintype "passive"))
    )
    (net (code "39") (name "Net-(BATT1_IC1-CCS)") (class "Default")
      (node (ref "BATT1_IC1") (pin "10") (pinfunction "CCS_10") (pintype "bidirectional"))
      (node (ref "C8") (pin "1") (pinfunction "1_1") (pintype "passive"))
    )
    (net (code "40") (name "Net-(BATT1_IC1-CCV)") (class "Default")
      (node (ref "BATT1_IC1") (pin "9") (pinfunction "CCV_9") (pintype "bidirectional"))
      (node (ref "C6") (pin "1") (pinfunction "1_1") (pintype "passive"))
      (node (ref "R5") (pin "2") (pinfunction "2_2") (pintype "passive"))
    )
    (net (code "41") (name "Net-(BATT1_IC1-CELL)") (class "Default")
      (node (ref "BATT1_IC1") (pin "1") (pinfunction "VL_1") (pintype "bidirectional"))
      (node (ref "BATT1_IC1") (pin "12") (pinfunction "CELL_12") (pintype "bidirectional"))
      (node (ref "C2") (pin "1") (pinfunction "1_1") (pintype "passive"))
      (node (ref "C3") (pin "1") (pinfunction "1_1") (pintype "passive"))
    )
    (net (code "42") (name "Net-(BATT1_IC1-CS)") (class "Default")
      (node (ref "BATT1_IC1") (pin "19") (pinfunction "CS_19") (pintype "bidirectional"))
      (node (ref "C14") (pin "1") (pinfunction "1_1") (pintype "passive"))
      (node (ref "L2") (pin "P$2") (pinfunction "2_P$2") (pintype "passive"))
      (node (ref "R7") (pin "2") (pinfunction "2_2") (pintype "passive"))
      (node (ref "R8") (pin "2") (pinfunction "2_2") (pintype "passive"))
    )
    (net (code "43") (name "Net-(BATT1_IC1-CSSN)") (class "Default")
      (node (ref "B1-ZENER1") (pin "C") (pinfunction "C_C") (pintype "passive"))
      (node (ref "BATT1_IC1") (pin "26") (pinfunction "CSSN_26") (pintype "bidirectional"))
      (node (ref "BATT1_IC1") (pin "27") (pinfunction "CSSP_27") (pintype "bidirectional"))
      (node (ref "BATT1_IC1") (pin "28") (pinfunction "DCIN_28") (pintype "bidirectional"))
      (node (ref "C1") (pin "1") (pinfunction "1_1") (pintype "passive"))
      (node (ref "NMOS5") (pin "TAB") (pinfunction "D_TAB") (pintype "bidirectional"))
    )
    (net (code "44") (name "Net-(BATT1_IC1-DHI)") (class "Default")
      (node (ref "BATT1_IC1") (pin "25") (pinfunction "DHI_25") (pintype "bidirectional"))
      (node (ref "NMOS5") (pin "1") (pinfunction "G_1") (pintype "bidirectional"))
    )
    (net (code "45") (name "Net-(BATT1_IC1-DLO)") (class "Default")
      (node (ref "BATT1_IC1") (pin "21") (pinfunction "DLO_21") (pintype "bidirectional"))
      (node (ref "NMOS6") (pin "1") (pinfunction "G_1") (pintype "bidirectional"))
    )
    (net (code "46") (name "Net-(BATT1_IC1-ISETIN)") (class "Default")
      (node (ref "BATT1_IC1") (pin "2") (pinfunction "ISETIN_2") (pintype "bidirectional"))
      (node (ref "BATT1_IC1") (pin "3") (pinfunction "ISETOUT_3") (pintype "bidirectional"))
      (node (ref "BATT1_IC1") (pin "5") (pinfunction "REF_5") (pintype "bidirectional"))
      (node (ref "C4") (pin "1") (pinfunction "1_1") (pintype "passive"))
      (node (ref "R2") (pin "1") (pinfunction "1_1") (pintype "passive"))
    )
    (net (code "47") (name "Net-(BATT1_IC1-LX)") (class "Default")
      (node (ref "BATT1_IC1") (pin "24") (pinfunction "LX_24") (pintype "bidirectional"))
      (node (ref "C12") (pin "1") (pinfunction "1_1") (pintype "passive"))
    )
    (net (code "48") (name "Net-(BATT1_IC1-PGND)") (class "Default")
      (node (ref "BATT1_IC1") (pin "20") (pinfunction "PGND_20") (pintype "bidirectional"))
      (node (ref "NMOS6") (pin "3") (pinfunction "S_3") (pintype "bidirectional"))
    )
    (net (code "49") (name "Net-(BATT1_IC1-THM)") (class "Default")
      (node (ref "BATT1_IC1") (pin "4") (pinfunction "THM_4") (pintype "bidirectional"))
      (node (ref "THERM2") (pin "P$1") (pinfunction "1_P$1") (pintype "passive"))
    )
    (net (code "50") (name "Net-(BATT1_IC1-TIMER1)") (class "Default")
      (node (ref "BATT1_IC1") (pin "13") (pinfunction "TIMER1_13") (pintype "bidirectional"))
      (node (ref "C9") (pin "1") (pinfunction "1_1") (pintype "passive"))
    )
    (net (code "51") (name "Net-(BATT1_IC1-TIMER2)") (class "Default")
      (node (ref "BATT1_IC1") (pin "14") (pinfunction "TIMER2_14") (pintype "bidirectional"))
      (node (ref "C10") (pin "1") (pinfunction "1_1") (pintype "passive"))
    )
    (net (code "52") (name "Net-(BATT1_IC1-VADJ)") (class "Default")
      (node (ref "BATT1_IC1") (pin "8") (pinfunction "VADJ_8") (pintype "bidirectional"))
      (node (ref "R2") (pin "2") (pinfunction "2_2") (pintype "passive"))
      (node (ref "R3") (pin "2") (pinfunction "2_2") (pintype "passive"))
    )
    (net (code "53") (name "Net-(BATT1_IC1-VLO)") (class "Default")
      (node (ref "BATT1_IC1") (pin "22") (pinfunction "VLO_22") (pintype "bidirectional"))
      (node (ref "C13") (pin "1") (pinfunction "1_1") (pintype "passive"))
      (node (ref "D2") (pin "A") (pinfunction "A_A") (pintype "passive"))
    )
    (net (code "54") (name "Net-(BUZZER-PadP$1)") (class "Default")
      (node (ref "BUZZER") (pin "P$1") (pinfunction "P$1_P$1") (pintype "bidirectional"))
      (node (ref "R13") (pin "2") (pinfunction "2_2") (pintype "passive"))
      (node (ref "R19") (pin "1") (pinfunction "1_1") (pintype "passive"))
    )
    (net (code "55") (name "Net-(BUZZER1-PadP$1)") (class "Default")
      (node (ref "BUZZER1") (pin "P$1") (pinfunction "P$1_P$1") (pintype "bidirectional"))
      (node (ref "R21") (pin "2") (pinfunction "2_2") (pintype "passive"))
      (node (ref "R22") (pin "1") (pinfunction "1_1") (pintype "passive"))
    )
    (net (code "56") (name "Net-(C5-Pad1)") (class "Default")
      (node (ref "C5") (pin "1") (pinfunction "1_1") (pintype "passive"))
      (node (ref "R5") (pin "1") (pinfunction "1_1") (pintype "passive"))
    )
    (net (code "57") (name "Net-(C17-Pad1)") (class "Default")
      (node (ref "C17") (pin "1") (pinfunction "1_1") (pintype "passive"))
      (node (ref "U$1") (pin "TMR") (pinfunction "TMR_TMR") (pintype "bidirectional"))
    )
    (net (code "58") (name "Net-(C64-Pad1)") (class "Default")
      (node (ref "C64") (pin "1") (pinfunction "1_1") (pintype "passive"))
      (node (ref "U$27") (pin "TMR") (pinfunction "TMR_TMR") (pintype "bidirectional"))
    )
    (net (code "59") (name "Net-(C70-Pad1)") (class "Default")
      (node (ref "C70") (pin "1") (pinfunction "1_1") (pintype "passive"))
      (node (ref "R32") (pin "1") (pinfunction "1_1") (pintype "passive"))
    )
    (net (code "60") (name "Net-(L1-1)") (class "Default")
      (node (ref "L1") (pin "P$1") (pinfunction "1_P$1") (pintype "passive"))
      (node (ref "NMOS1") (pin "3") (pinfunction "S_3") (pintype "bidirectional"))
      (node (ref "NMOS2") (pin "TAB") (pinfunction "D_TAB") (pintype "bidirectional"))
    )
    (net (code "61") (name "Net-(L2-1)") (class "Default")
      (node (ref "L2") (pin "P$1") (pinfunction "1_P$1") (pintype "passive"))
      (node (ref "NMOS5") (pin "3") (pinfunction "S_3") (pintype "bidirectional"))
      (node (ref "NMOS6") (pin "TAB") (pinfunction "D_TAB") (pintype "bidirectional"))
    )
    (net (code "62") (name "Net-(LED1-PadA)") (class "Default")
      (node (ref "LED1") (pin "A") (pinfunction "A_A") (pintype "passive"))
      (node (ref "R9") (pin "1") (pinfunction "1_1") (pintype "passive"))
    )
    (net (code "63") (name "Net-(LED2-PadA)") (class "Default")
      (node (ref "LED2") (pin "A") (pinfunction "A_A") (pintype "passive"))
      (node (ref "R11") (pin "1") (pinfunction "1_1") (pintype "passive"))
    )
    (net (code "64") (name "Net-(LED3-PadA)") (class "Default")
      (node (ref "LED3") (pin "A") (pinfunction "A_A") (pintype "passive"))
      (node (ref "R13") (pin "1") (pinfunction "1_1") (pintype "passive"))
    )
    (net (code "65") (name "Net-(LED4-PadA)") (class "Default")
      (node (ref "LED4") (pin "A") (pinfunction "A_A") (pintype "passive"))
      (node (ref "R1") (pin "1") (pinfunction "1_1") (pintype "passive"))
    )
    (net (code "66") (name "Net-(LED5-PadA)") (class "Default")
      (node (ref "LED5") (pin "A") (pinfunction "A_A") (pintype "passive"))
      (node (ref "R15") (pin "1") (pinfunction "1_1") (pintype "passive"))
    )
    (net (code "67") (name "Net-(LED6-PadA)") (class "Default")
      (node (ref "LED6") (pin "A") (pinfunction "A_A") (pintype "passive"))
      (node (ref "R17") (pin "1") (pinfunction "1_1") (pintype "passive"))
    )
    (net (code "68") (name "Net-(LED7-PadA)") (class "Default")
      (node (ref "LED7") (pin "A") (pinfunction "A_A") (pintype "passive"))
      (node (ref "R28") (pin "1") (pinfunction "1_1") (pintype "passive"))
    )
    (net (code "69") (name "Net-(LED8-PadA)") (class "Default")
      (node (ref "LED8") (pin "A") (pinfunction "A_A") (pintype "passive"))
      (node (ref "R33") (pin "1") (pinfunction "1_1") (pintype "passive"))
    )
    (net (code "70") (name "Net-(LED9-PadA)") (class "Default")
      (node (ref "LED9") (pin "A") (pinfunction "A_A") (pintype "passive"))
      (node (ref "R21") (pin "1") (pinfunction "1_1") (pintype "passive"))
    )
    (net (code "71") (name "Net-(LED10-PadA)") (class "Default")
      (node (ref "LED10") (pin "A") (pinfunction "A_A") (pintype "passive"))
      (node (ref "R51") (pin "1") (pinfunction "1_1") (pintype "passive"))
    )
    (net (code "72") (name "Net-(LED11-PadA)") (class "Default")
      (node (ref "LED11") (pin "A") (pinfunction "A_A") (pintype "passive"))
      (node (ref "R54") (pin "1") (pinfunction "1_1") (pintype "passive"))
    )
    (net (code "73") (name "Net-(LED12-PadC)") (class "Default")
      (node (ref "LED12") (pin "C") (pinfunction "C_C") (pintype "passive"))
      (node (ref "R56") (pin "2") (pinfunction "2_2") (pintype "passive"))
    )
    (net (code "74") (name "Net-(LED13-PadC)") (class "Default")
      (node (ref "LED13") (pin "C") (pinfunction "C_C") (pintype "passive"))
      (node (ref "R58") (pin "2") (pinfunction "2_2") (pintype "passive"))
    )
    (net (code "75") (name "Net-(LED14-A)") (class "Default")
      (node (ref "LED14") (pin "P$1") (pinfunction "A_P$1") (pintype "passive"))
      (node (ref "R60") (pin "1") (pinfunction "1_1") (pintype "passive"))
      (node (ref "U$11") (pin "P$1") (pinfunction "C_P$1") (pintype "passive"))
    )
    (net (code "76") (name "Net-(LED15-A)") (class "Default")
      (node (ref "LED15") (pin "P$1") (pinfunction "A_P$1") (pintype "passive"))
      (node (ref "R61") (pin "1") (pinfunction "1_1") (pintype "passive"))
      (node (ref "U$12") (pin "P$1") (pinfunction "C_P$1") (pintype "passive"))
    )
    (net (code "77") (name "Net-(LED16-A)") (class "Default")
      (node (ref "LED16") (pin "P$1") (pinfunction "A_P$1") (pintype "passive"))
      (node (ref "R62") (pin "1") (pinfunction "1_1") (pintype "passive"))
    )
    (net (code "78") (name "Net-(LED17-A)") (class "Default")
      (node (ref "LED17") (pin "P$1") (pinfunction "A_P$1") (pintype "passive"))
      (node (ref "R63") (pin "1") (pinfunction "1_1") (pintype "passive"))
    )
    (net (code "79") (name "Net-(LED18-PadA)") (class "Default")
      (node (ref "LED18") (pin "A") (pinfunction "A_A") (pintype "passive"))
      (node (ref "R4") (pin "1") (pinfunction "1_1") (pintype "passive"))
    )
    (net (code "80") (name "Net-(LED19-PadA)") (class "Default")
      (node (ref "LED19") (pin "A") (pinfunction "A_A") (pintype "passive"))
      (node (ref "R6") (pin "1") (pinfunction "1_1") (pintype "passive"))
    )
    (net (code "81") (name "Net-(POT-S)") (class "Default")
      (node (ref "POT") (pin "2") (pinfunction "S_2") (pintype "passive"))
      (node (ref "TEST-PTS") (pin "2") (pinfunction "2_2") (pintype "passive"))
      (node (ref "U$11") (pin "P$2") (pinfunction "REF_P$2") (pintype "bidirectional"))
    )
    (net (code "82") (name "Net-(POT1-S)") (class "Default")
      (node (ref "POT1") (pin "2") (pinfunction "S_2") (pintype "passive"))
      (node (ref "TEST-PTS1") (pin "2") (pinfunction "2_2") (pintype "passive"))
      (node (ref "U$12") (pin "P$2") (pinfunction "REF_P$2") (pintype "bidirectional"))
    )
    (net (code "83") (name "Net-(R27-Pad2)") (class "Default")
      (node (ref "R27") (pin "2") (pinfunction "2_2") (pintype "passive"))
      (node (ref "R38") (pin "1") (pinfunction "1_1") (pintype "passive"))
      (node (ref "U$27") (pin "UV") (pinfunction "UV_UV") (pintype "bidirectional"))
    )
    (net (code "84") (name "Net-(R35-Pad1)") (class "Default")
      (node (ref "R35") (pin "1") (pinfunction "1_1") (pintype "passive"))
      (node (ref "R40") (pin "2") (pinfunction "2_2") (pintype "passive"))
      (node (ref "U$27") (pin "FB") (pinfunction "FB_FB") (pintype "bidirectional"))
    )
    (net (code "85") (name "Net-(R35-Pad2)") (class "Default")
      (node (ref "R35") (pin "2") (pinfunction "2_2") (pintype "passive"))
      (node (ref "R39") (pin "1") (pinfunction "1_1") (pintype "passive"))
    )
    (net (code "86") (name "Net-(R37-Pad1)") (class "Default")
      (node (ref "R37") (pin "1") (pinfunction "1_1") (pintype "passive"))
      (node (ref "U$27") (pin "HGATE") (pinfunction "HGATE_HGATE") (pintype "bidirectional"))
    )
    (net (code "87") (name "Net-(R41-Pad2)") (class "Default")
      (node (ref "R41") (pin "2") (pinfunction "2_2") (pintype "passive"))
      (node (ref "R45") (pin "1") (pinfunction "1_1") (pintype "passive"))
      (node (ref "U$1") (pin "UV") (pinfunction "UV_UV") (pintype "bidirectional"))
    )
    (net (code "88") (name "Net-(R42-Pad1)") (class "Default")
      (node (ref "R42") (pin "1") (pinfunction "1_1") (pintype "passive"))
      (node (ref "R47") (pin "2") (pinfunction "2_2") (pintype "passive"))
      (node (ref "U$1") (pin "FB") (pinfunction "FB_FB") (pintype "bidirectional"))
    )
    (net (code "89") (name "Net-(R42-Pad2)") (class "Default")
      (node (ref "R42") (pin "2") (pinfunction "2_2") (pintype "passive"))
      (node (ref "R46") (pin "1") (pinfunction "1_1") (pintype "passive"))
    )
    (net (code "90") (name "Net-(R44-Pad1)") (class "Default")
      (node (ref "R44") (pin "1") (pinfunction "1_1") (pintype "passive"))
      (node (ref "U$1") (pin "HGATE") (pinfunction "HGATE_HGATE") (pintype "bidirectional"))
    )
    (net (code "91") (name "Net-(U$2-G)") (class "Default")
      (node (ref "R44") (pin "2") (pinfunction "2_2") (pintype "passive"))
      (node (ref "U$2") (pin "1") (pinfunction "G_1") (pintype "bidirectional"))
    )
    (net (code "92") (name "Net-(U$2-S)") (class "Default")
      (node (ref "U$1") (pin "SOURCE") (pinfunction "SOURCE_SOURCE") (pintype "bidirectional"))
      (node (ref "U$2") (pin "3") (pinfunction "S_3") (pintype "bidirectional"))
      (node (ref "U$3") (pin "3") (pinfunction "S_3") (pintype "bidirectional"))
    )
    (net (code "93") (name "Net-(U$3-D)") (class "Default")
      (node (ref "R43") (pin "1") (pinfunction "1_1") (pintype "passive"))
      (node (ref "U$1") (pin "SENSE") (pinfunction "SENSE_SENSE") (pintype "bidirectional"))
      (node (ref "U$3") (pin "TAB") (pinfunction "D_TAB") (pintype "bidirectional"))
    )
    (net (code "94") (name "Net-(U$3-G)") (class "Default")
      (node (ref "U$1") (pin "DGATE") (pinfunction "DGATE_DGATE") (pintype "bidirectional"))
      (node (ref "U$3") (pin "1") (pinfunction "G_1") (pintype "bidirectional"))
    )
    (net (code "95") (name "Net-(U$7-S)") (class "Default")
      (node (ref "R52") (pin "2") (pinfunction "2_2") (pintype "passive"))
      (node (ref "U$7") (pin "P$3") (pinfunction "S_P$3") (pintype "bidirectional"))
    )
    (net (code "96") (name "Net-(U$8-S)") (class "Default")
      (node (ref "R55") (pin "2") (pinfunction "2_2") (pintype "passive"))
      (node (ref "U$8") (pin "P$3") (pinfunction "S_P$3") (pintype "bidirectional"))
    )
    (net (code "97") (name "Net-(U$9-D)") (class "Default")
      (node (ref "R56") (pin "1") (pinfunction "1_1") (pintype "passive"))
      (node (ref "U$9") (pin "3") (pinfunction "D_3") (pintype "bidirectional"))
    )
    (net (code "98") (name "Net-(U$10-D)") (class "Default")
      (node (ref "R58") (pin "1") (pinfunction "1_1") (pintype "passive"))
      (node (ref "U$10") (pin "3") (pinfunction "D_3") (pintype "bidirectional"))
    )
    (net (code "99") (name "Net-(U$28-G)") (class "Default")
      (node (ref "R37") (pin "2") (pinfunction "2_2") (pintype "passive"))
      (node (ref "U$28") (pin "1") (pinfunction "G_1") (pintype "bidirectional"))
    )
    (net (code "100") (name "Net-(U$28-S)") (class "Default")
      (node (ref "U$27") (pin "SOURCE") (pinfunction "SOURCE_SOURCE") (pintype "bidirectional"))
      (node (ref "U$28") (pin "3") (pinfunction "S_3") (pintype "bidirectional"))
      (node (ref "U$32") (pin "3") (pinfunction "S_3") (pintype "bidirectional"))
    )
    (net (code "101") (name "Net-(U$32-D)") (class "Default")
      (node (ref "R36") (pin "1") (pinfunction "1_1") (pintype "passive"))
      (node (ref "U$27") (pin "SENSE") (pinfunction "SENSE_SENSE") (pintype "bidirectional"))
      (node (ref "U$32") (pin "TAB") (pinfunction "D_TAB") (pintype "bidirectional"))
    )
    (net (code "102") (name "Net-(U$32-G)") (class "Default")
      (node (ref "U$27") (pin "DGATE") (pinfunction "DGATE_DGATE") (pintype "bidirectional"))
      (node (ref "U$32") (pin "1") (pinfunction "G_1") (pintype "bidirectional"))
    )
    (net (code "103") (name "Net-(U1-D)") (class "Default")
      (node (ref "R15") (pin "2") (pinfunction "2_2") (pintype "passive"))
      (node (ref "U1") (pin "P$2") (pinfunction "D_P$2") (pintype "bidirectional"))
    )
    (net (code "104") (name "Net-(U2-D)") (class "Default")
      (node (ref "R17") (pin "2") (pinfunction "2_2") (pintype "passive"))
      (node (ref "U2") (pin "P$2") (pinfunction "D_P$2") (pintype "bidirectional"))
    )
    (net (code "105") (name "Net-(U3-D)") (class "Default")
      (node (ref "R22") (pin "2") (pinfunction "2_2") (pintype "passive"))
      (node (ref "U3") (pin "P$2") (pinfunction "D_P$2") (pintype "bidirectional"))
    )
    (net (code "106") (name "Net-(U7-D)") (class "Default")
      (node (ref "R9") (pin "2") (pinfunction "2_2") (pintype "passive"))
      (node (ref "U7") (pin "P$2") (pinfunction "D_P$2") (pintype "bidirectional"))
    )
    (net (code "107") (name "Net-(U8-D)") (class "Default")
      (node (ref "R11") (pin "2") (pinfunction "2_2") (pintype "passive"))
      (node (ref "U8") (pin "P$2") (pinfunction "D_P$2") (pintype "bidirectional"))
    )
    (net (code "108") (name "Net-(U9-D)") (class "Default")
      (node (ref "R19") (pin "2") (pinfunction "2_2") (pintype "passive"))
      (node (ref "U9") (pin "P$2") (pinfunction "D_P$2") (pintype "bidirectional"))
    )
    (net (code "109") (name "Net-(U56-IN)") (class "Default")
      (node (ref "C60") (pin "1") (pinfunction "1_1") (pintype "passive"))
      (node (ref "R23") (pin "2") (pinfunction "2_2") (pintype "passive"))
      (node (ref "U56") (pin "P$2") (pinfunction "IN_P$2") (pintype "bidirectional"))
    )
    (net (code "110") (name "ORING1_ENOUT") (class "Default")
      (node (ref "U$1") (pin "ENOUT") (pinfunction "ENOUT_ENOUT") (pintype "bidirectional"))
    )
    (net (code "111") (name "ORING2_ENOUT") (class "Default")
      (node (ref "R57") (pin "1") (pinfunction "1_1") (pintype "passive"))
      (node (ref "U$27") (pin "ENOUT") (pinfunction "ENOUT_ENOUT") (pintype "bidirectional"))
      (node (ref "U$9") (pin "1") (pinfunction "G_1") (pintype "passive"))
    )
    (net (code "112") (name "ORING_ENOUT") (class "Default")
      (node (ref "R59") (pin "1") (pinfunction "1_1") (pintype "passive"))
      (node (ref "U$10") (pin "1") (pinfunction "G_1") (pintype "passive"))
    )
    (net (code "113") (name "V_BATT") (class "Default")
      (node (ref "24V-TVS-6") (pin "P$2") (pinfunction "C_P$2") (pintype "passive"))
      (node (ref "24V-TVS-7") (pin "P$2") (pinfunction "C_P$2") (pintype "passive"))
      (node (ref "24V-TVS-8") (pin "P$2") (pinfunction "C_P$2") (pintype "passive"))
      (node (ref "24V-TVS-9") (pin "P$2") (pinfunction "C_P$2") (pintype "passive"))
      (node (ref "C18") (pin "1") (pinfunction "1_1") (pintype "passive"))
      (node (ref "C65") (pin "1") (pinfunction "1_1") (pintype "passive"))
      (node (ref "JP1") (pin "1") (pinfunction "P$1_1") (pintype "bidirectional"))
      (node (ref "JP1") (pin "10") (pinfunction "P$10_10") (pintype "bidirectional"))
      (node (ref "JP1") (pin "2") (pinfunction "P$2_2") (pintype "bidirectional"))
      (node (ref "JP1") (pin "21") (pinfunction "P$21_21") (pintype "bidirectional"))
      (node (ref "JP1") (pin "22") (pinfunction "P$22_22") (pintype "bidirectional"))
      (node (ref "JP1") (pin "23") (pinfunction "P$23_23") (pintype "bidirectional"))
      (node (ref "JP1") (pin "24") (pinfunction "P$24_24") (pintype "bidirectional"))
      (node (ref "JP1") (pin "25") (pinfunction "P$25_25") (pintype "bidirectional"))
      (node (ref "JP1") (pin "26") (pinfunction "P$26_26") (pintype "bidirectional"))
      (node (ref "JP1") (pin "27") (pinfunction "P$27_27") (pintype "bidirectional"))
      (node (ref "JP1") (pin "28") (pinfunction "P$28_28") (pintype "bidirectional"))
      (node (ref "JP1") (pin "29") (pinfunction "P$29_29") (pintype "bidirectional"))
      (node (ref "JP1") (pin "3") (pinfunction "P$3_3") (pintype "bidirectional"))
      (node (ref "JP1") (pin "30") (pinfunction "P$30_30") (pintype "bidirectional"))
      (node (ref "JP1") (pin "4") (pinfunction "P$4_4") (pintype "bidirectional"))
      (node (ref "JP1") (pin "41") (pinfunction "P$41_41") (pintype "bidirectional"))
      (node (ref "JP1") (pin "42") (pinfunction "P$42_42") (pintype "bidirectional"))
      (node (ref "JP1") (pin "43") (pinfunction "P$43_43") (pintype "bidirectional"))
      (node (ref "JP1") (pin "44") (pinfunction "P$44_44") (pintype "bidirectional"))
      (node (ref "JP1") (pin "45") (pinfunction "P$45_45") (pintype "bidirectional"))
      (node (ref "JP1") (pin "46") (pinfunction "P$46_46") (pintype "bidirectional"))
      (node (ref "JP1") (pin "47") (pinfunction "P$47_47") (pintype "bidirectional"))
      (node (ref "JP1") (pin "48") (pinfunction "P$48_48") (pintype "bidirectional"))
      (node (ref "JP1") (pin "49") (pinfunction "P$49_49") (pintype "bidirectional"))
      (node (ref "JP1") (pin "5") (pinfunction "P$5_5") (pintype "bidirectional"))
      (node (ref "JP1") (pin "50") (pinfunction "P$50_50") (pintype "bidirectional"))
      (node (ref "JP1") (pin "6") (pinfunction "P$6_6") (pintype "bidirectional"))
      (node (ref "JP1") (pin "61") (pinfunction "P$61_61") (pintype "bidirectional"))
      (node (ref "JP1") (pin "62") (pinfunction "P$62_62") (pintype "bidirectional"))
      (node (ref "JP1") (pin "63") (pinfunction "P$63_63") (pintype "bidirectional"))
      (node (ref "JP1") (pin "64") (pinfunction "P$64_64") (pintype "bidirectional"))
      (node (ref "JP1") (pin "65") (pinfunction "P$65_65") (pintype "bidirectional"))
      (node (ref "JP1") (pin "66") (pinfunction "P$66_66") (pintype "bidirectional"))
      (node (ref "JP1") (pin "67") (pinfunction "P$67_67") (pintype "bidirectional"))
      (node (ref "JP1") (pin "68") (pinfunction "P$68_68") (pintype "bidirectional"))
      (node (ref "JP1") (pin "69") (pinfunction "P$69_69") (pintype "bidirectional"))
      (node (ref "JP1") (pin "7") (pinfunction "P$7_7") (pintype "bidirectional"))
      (node (ref "JP1") (pin "70") (pinfunction "P$70_70") (pintype "bidirectional"))
      (node (ref "JP1") (pin "8") (pinfunction "P$8_8") (pintype "bidirectional"))
      (node (ref "JP1") (pin "9") (pinfunction "P$9_9") (pintype "bidirectional"))
      (node (ref "R36") (pin "2") (pinfunction "2_2") (pintype "passive"))
      (node (ref "R39") (pin "2") (pinfunction "2_2") (pintype "passive"))
      (node (ref "R43") (pin "2") (pinfunction "2_2") (pintype "passive"))
      (node (ref "R46") (pin "2") (pinfunction "2_2") (pintype "passive"))
      (node (ref "U$1") (pin "OUT") (pinfunction "OUT_OUT") (pintype "bidirectional"))
      (node (ref "U$27") (pin "OUT") (pinfunction "OUT_OUT") (pintype "bidirectional"))
    )
    (net (code "114") (name "V_BATT1") (class "Default")
      (node (ref "C25") (pin "1") (pinfunction "1_1") (pintype "passive"))
      (node (ref "C61") (pin "1") (pinfunction "1_1") (pintype "passive"))
      (node (ref "LED12") (pin "A") (pinfunction "A_A") (pintype "passive"))
      (node (ref "POT1") (pin "3") (pinfunction "A_3") (pintype "passive"))
      (node (ref "R1") (pin "2") (pinfunction "2_2") (pintype "passive"))
      (node (ref "R45") (pin "2") (pinfunction "2_2") (pintype "passive"))
      (node (ref "R53") (pin "2") (pinfunction "2_2") (pintype "passive"))
      (node (ref "R57") (pin "2") (pinfunction "2_2") (pintype "passive"))
      (node (ref "R61") (pin "2") (pinfunction "2_2") (pintype "passive"))
      (node (ref "R63") (pin "2") (pinfunction "2_2") (pintype "passive"))
      (node (ref "U$1") (pin "VCC") (pinfunction "VCC_VCC") (pintype "bidirectional"))
      (node (ref "U$2") (pin "TAB") (pinfunction "D_TAB") (pintype "bidirectional"))
      (node (ref "U$8") (pin "P$2") (pinfunction "D_P$2") (pintype "bidirectional"))
      (node (ref "U57") (pin "P$3") (pinfunction "VIN_P$3") (pintype "bidirectional"))
    )
    (net (code "115") (name "V_BATT2") (class "Default")
      (node (ref "C26") (pin "1") (pinfunction "1_1") (pintype "passive"))
      (node (ref "LED13") (pin "A") (pinfunction "A_A") (pintype "passive"))
      (node (ref "POT") (pin "3") (pinfunction "A_3") (pintype "passive"))
      (node (ref "R38") (pin "2") (pinfunction "2_2") (pintype "passive"))
      (node (ref "R4") (pin "2") (pinfunction "2_2") (pintype "passive"))
      (node (ref "R50") (pin "2") (pinfunction "2_2") (pintype "passive"))
      (node (ref "R59") (pin "2") (pinfunction "2_2") (pintype "passive"))
      (node (ref "R60") (pin "2") (pinfunction "2_2") (pintype "passive"))
      (node (ref "R62") (pin "2") (pinfunction "2_2") (pintype "passive"))
      (node (ref "U$27") (pin "VCC") (pinfunction "VCC_VCC") (pintype "bidirectional"))
      (node (ref "U$28") (pin "TAB") (pinfunction "D_TAB") (pintype "bidirectional"))
      (node (ref "U$7") (pin "P$2") (pinfunction "D_P$2") (pintype "bidirectional"))
    )
    (net (code "116") (name "V_SHORE") (class "Default")
      (node (ref "24V-TVS-1") (pin "P$2") (pinfunction "C_P$2") (pintype "passive"))
      (node (ref "24V-TVS-2") (pin "P$2") (pinfunction "C_P$2") (pintype "passive"))
      (node (ref "24V-TVS-4") (pin "P$2") (pinfunction "C_P$2") (pintype "passive"))
      (node (ref "24V-TVS-5") (pin "P$2") (pinfunction "C_P$2") (pintype "passive"))
      (node (ref "24V-TVS_1") (pin "P$2") (pinfunction "C_P$2") (pintype "passive"))
      (node (ref "B1-ZENER") (pin "A") (pinfunction "A_A") (pintype "passive"))
      (node (ref "B1-ZENER1") (pin "A") (pinfunction "A_A") (pintype "passive"))
      (node (ref "JP1") (pin "11") (pinfunction "P$11_11") (pintype "bidirectional"))
      (node (ref "JP1") (pin "12") (pinfunction "P$12_12") (pintype "bidirectional"))
      (node (ref "JP1") (pin "13") (pinfunction "P$13_13") (pintype "bidirectional"))
      (node (ref "JP1") (pin "14") (pinfunction "P$14_14") (pintype "bidirectional"))
      (node (ref "JP1") (pin "15") (pinfunction "P$15_15") (pintype "bidirectional"))
      (node (ref "JP1") (pin "16") (pinfunction "P$16_16") (pintype "bidirectional"))
      (node (ref "JP1") (pin "17") (pinfunction "P$17_17") (pintype "bidirectional"))
      (node (ref "JP1") (pin "18") (pinfunction "P$18_18") (pintype "bidirectional"))
      (node (ref "JP1") (pin "19") (pinfunction "P$19_19") (pintype "bidirectional"))
      (node (ref "JP1") (pin "20") (pinfunction "P$20_20") (pintype "bidirectional"))
      (node (ref "JP1") (pin "31") (pinfunction "P$31_31") (pintype "bidirectional"))
      (node (ref "JP1") (pin "32") (pinfunction "P$32_32") (pintype "bidirectional"))
      (node (ref "JP1") (pin "33") (pinfunction "P$33_33") (pintype "bidirectional"))
      (node (ref "JP1") (pin "34") (pinfunction "P$34_34") (pintype "bidirectional"))
      (node (ref "JP1") (pin "35") (pinfunction "P$35_35") (pintype "bidirectional"))
      (node (ref "JP1") (pin "36") (pinfunction "P$36_36") (pintype "bidirectional"))
      (node (ref "JP1") (pin "37") (pinfunction "P$37_37") (pintype "bidirectional"))
      (node (ref "JP1") (pin "38") (pinfunction "P$38_38") (pintype "bidirectional"))
      (node (ref "JP1") (pin "39") (pinfunction "P$39_39") (pintype "bidirectional"))
      (node (ref "JP1") (pin "40") (pinfunction "P$40_40") (pintype "bidirectional"))
      (node (ref "JP1") (pin "51") (pinfunction "P$51_51") (pintype "bidirectional"))
      (node (ref "JP1") (pin "52") (pinfunction "P$52_52") (pintype "bidirectional"))
      (node (ref "JP1") (pin "53") (pinfunction "P$53_53") (pintype "bidirectional"))
      (node (ref "JP1") (pin "54") (pinfunction "P$54_54") (pintype "bidirectional"))
      (node (ref "JP1") (pin "55") (pinfunction "P$55_55") (pintype "bidirectional"))
      (node (ref "JP1") (pin "56") (pinfunction "P$56_56") (pintype "bidirectional"))
      (node (ref "JP1") (pin "57") (pinfunction "P$57_57") (pintype "bidirectional"))
      (node (ref "JP1") (pin "58") (pinfunction "P$58_58") (pintype "bidirectional"))
      (node (ref "JP1") (pin "59") (pinfunction "P$59_59") (pintype "bidirectional"))
      (node (ref "JP1") (pin "60") (pinfunction "P$60_60") (pintype "bidirectional"))
      (node (ref "JP1") (pin "71") (pinfunction "P$71_71") (pintype "bidirectional"))
      (node (ref "JP1") (pin "72") (pinfunction "P$72_72") (pintype "bidirectional"))
      (node (ref "JP1") (pin "73") (pinfunction "P$73_73") (pintype "bidirectional"))
      (node (ref "JP1") (pin "74") (pinfunction "P$74_74") (pintype "bidirectional"))
      (node (ref "JP1") (pin "75") (pinfunction "P$75_75") (pintype "bidirectional"))
      (node (ref "JP1") (pin "76") (pinfunction "P$76_76") (pintype "bidirectional"))
      (node (ref "JP1") (pin "77") (pinfunction "P$77_77") (pintype "bidirectional"))
      (node (ref "JP1") (pin "78") (pinfunction "P$78_78") (pintype "bidirectional"))
      (node (ref "JP1") (pin "79") (pinfunction "P$79_79") (pintype "bidirectional"))
      (node (ref "JP1") (pin "80") (pinfunction "P$80_80") (pintype "bidirectional"))
      (node (ref "R10") (pin "2") (pinfunction "2_2") (pintype "passive"))
      (node (ref "R12") (pin "2") (pinfunction "2_2") (pintype "passive"))
      (node (ref "R14") (pin "2") (pinfunction "2_2") (pintype "passive"))
      (node (ref "R16") (pin "2") (pinfunction "2_2") (pintype "passive"))
      (node (ref "R18") (pin "2") (pinfunction "2_2") (pintype "passive"))
      (node (ref "R20") (pin "2") (pinfunction "2_2") (pintype "passive"))
      (node (ref "R28") (pin "2") (pinfunction "2_2") (pintype "passive"))
      (node (ref "SHORE_IN") (pin "P$1") (pinfunction "P$1_P$1") (pintype "bidirectional"))
      (node (ref "U1") (pin "P$3") (pinfunction "S_P$3") (pintype "bidirectional"))
      (node (ref "U2") (pin "P$3") (pinfunction "S_P$3") (pintype "bidirectional"))
      (node (ref "U3") (pin "P$3") (pinfunction "S_P$3") (pintype "bidirectional"))
      (node (ref "U7") (pin "P$3") (pinfunction "S_P$3") (pintype "bidirectional"))
      (node (ref "U8") (pin "P$3") (pinfunction "S_P$3") (pintype "bidirectional"))
      (node (ref "U9") (pin "P$3") (pinfunction "S_P$3") (pintype "bidirectional"))
    )
    (net (code "117") (name "unconnected-(5-TVS_1-PadP$3)") (class "Default")
      (node (ref "5-TVS_1") (pin "P$3") (pinfunction "P$3_P$3") (pintype "bidirectional"))
    )
    (net (code "118") (name "unconnected-(5-TVS_1-PadP$4)") (class "Default")
      (node (ref "5-TVS_1") (pin "P$4") (pinfunction "P$4_P$4") (pintype "bidirectional"))
    )
    (net (code "119") (name "unconnected-(5-TVS_1-PadP$5)") (class "Default")
      (node (ref "5-TVS_1") (pin "P$5") (pinfunction "P$5_P$5") (pintype "bidirectional"))
    )
    (net (code "120") (name "unconnected-(5-TVS_1-PadP$6)") (class "Default")
      (node (ref "5-TVS_1") (pin "P$6") (pinfunction "P$6_P$6") (pintype "bidirectional"))
    )
  )
)
